# Private_CPU_Power.net
KiCad netlist of a schematic drawn in Altium Designer
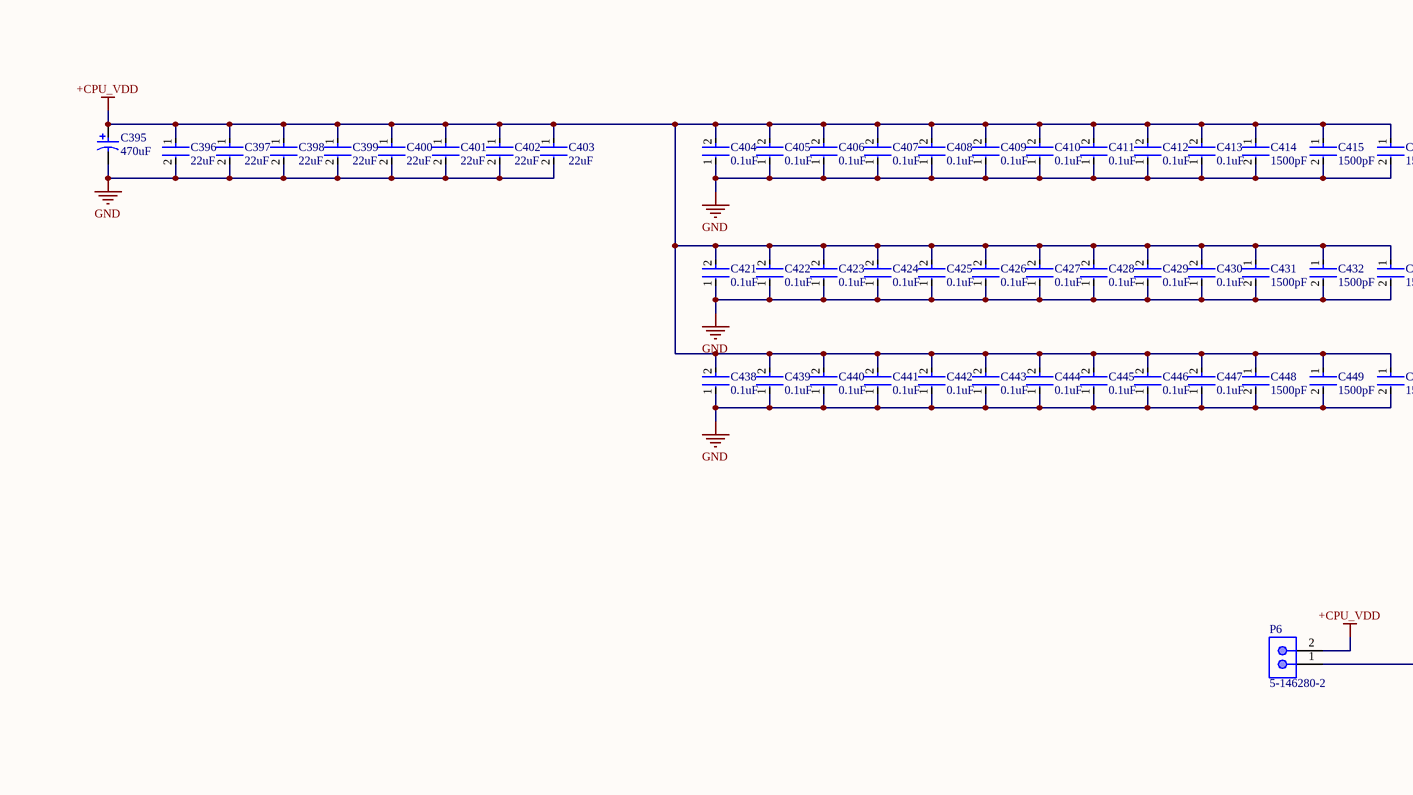
[diagram p0: Private_CPU_Power.SchDoc, top left]
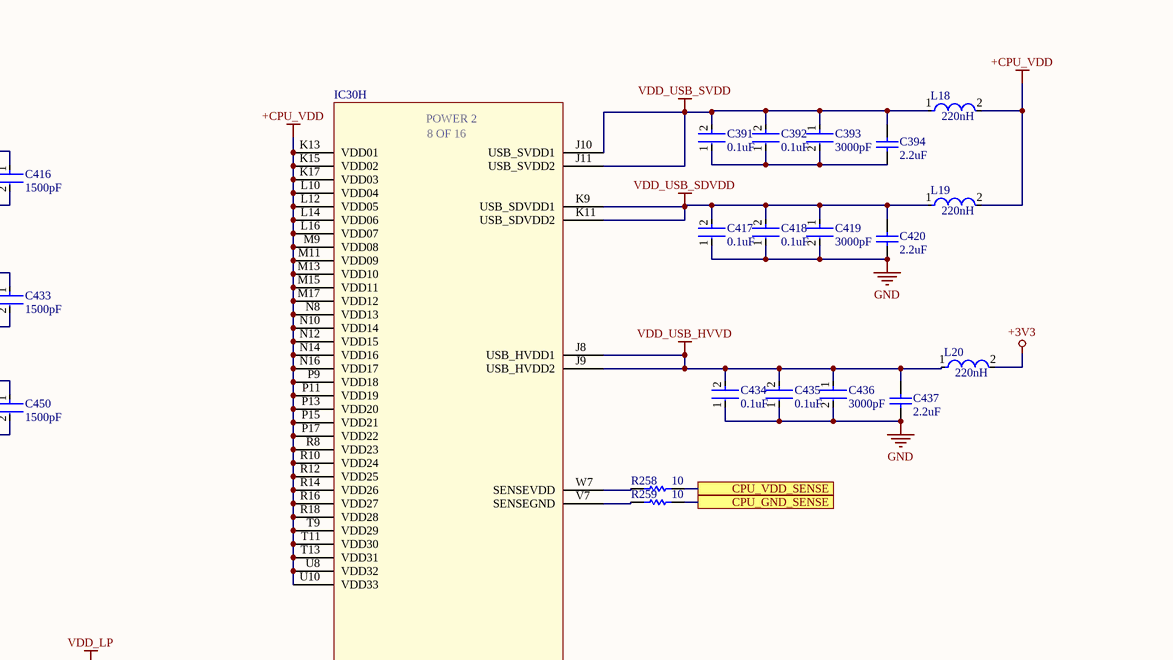
[diagram p1: Private_CPU_Power.SchDoc, top right]
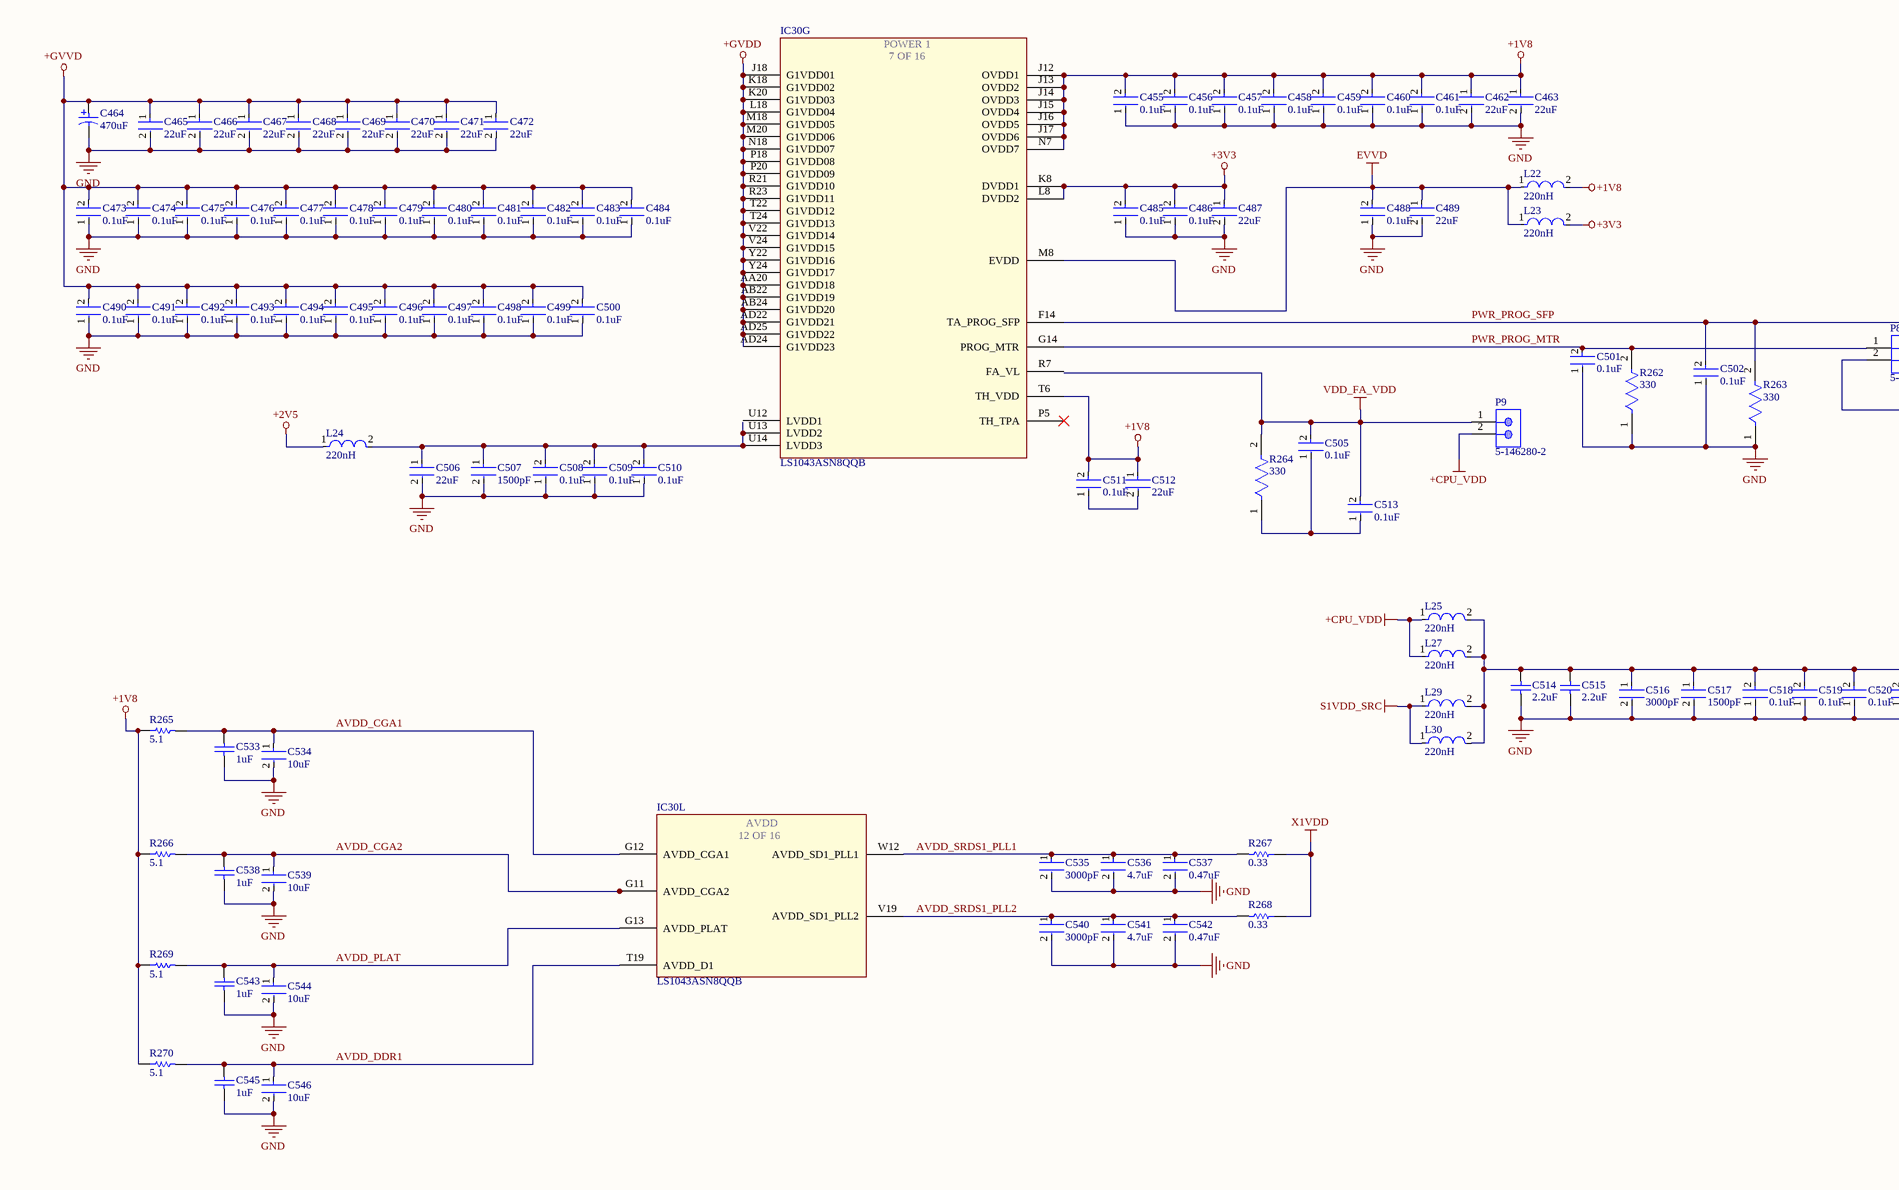
[diagram p2: Private_CPU_Power.SchDoc, bottom left]
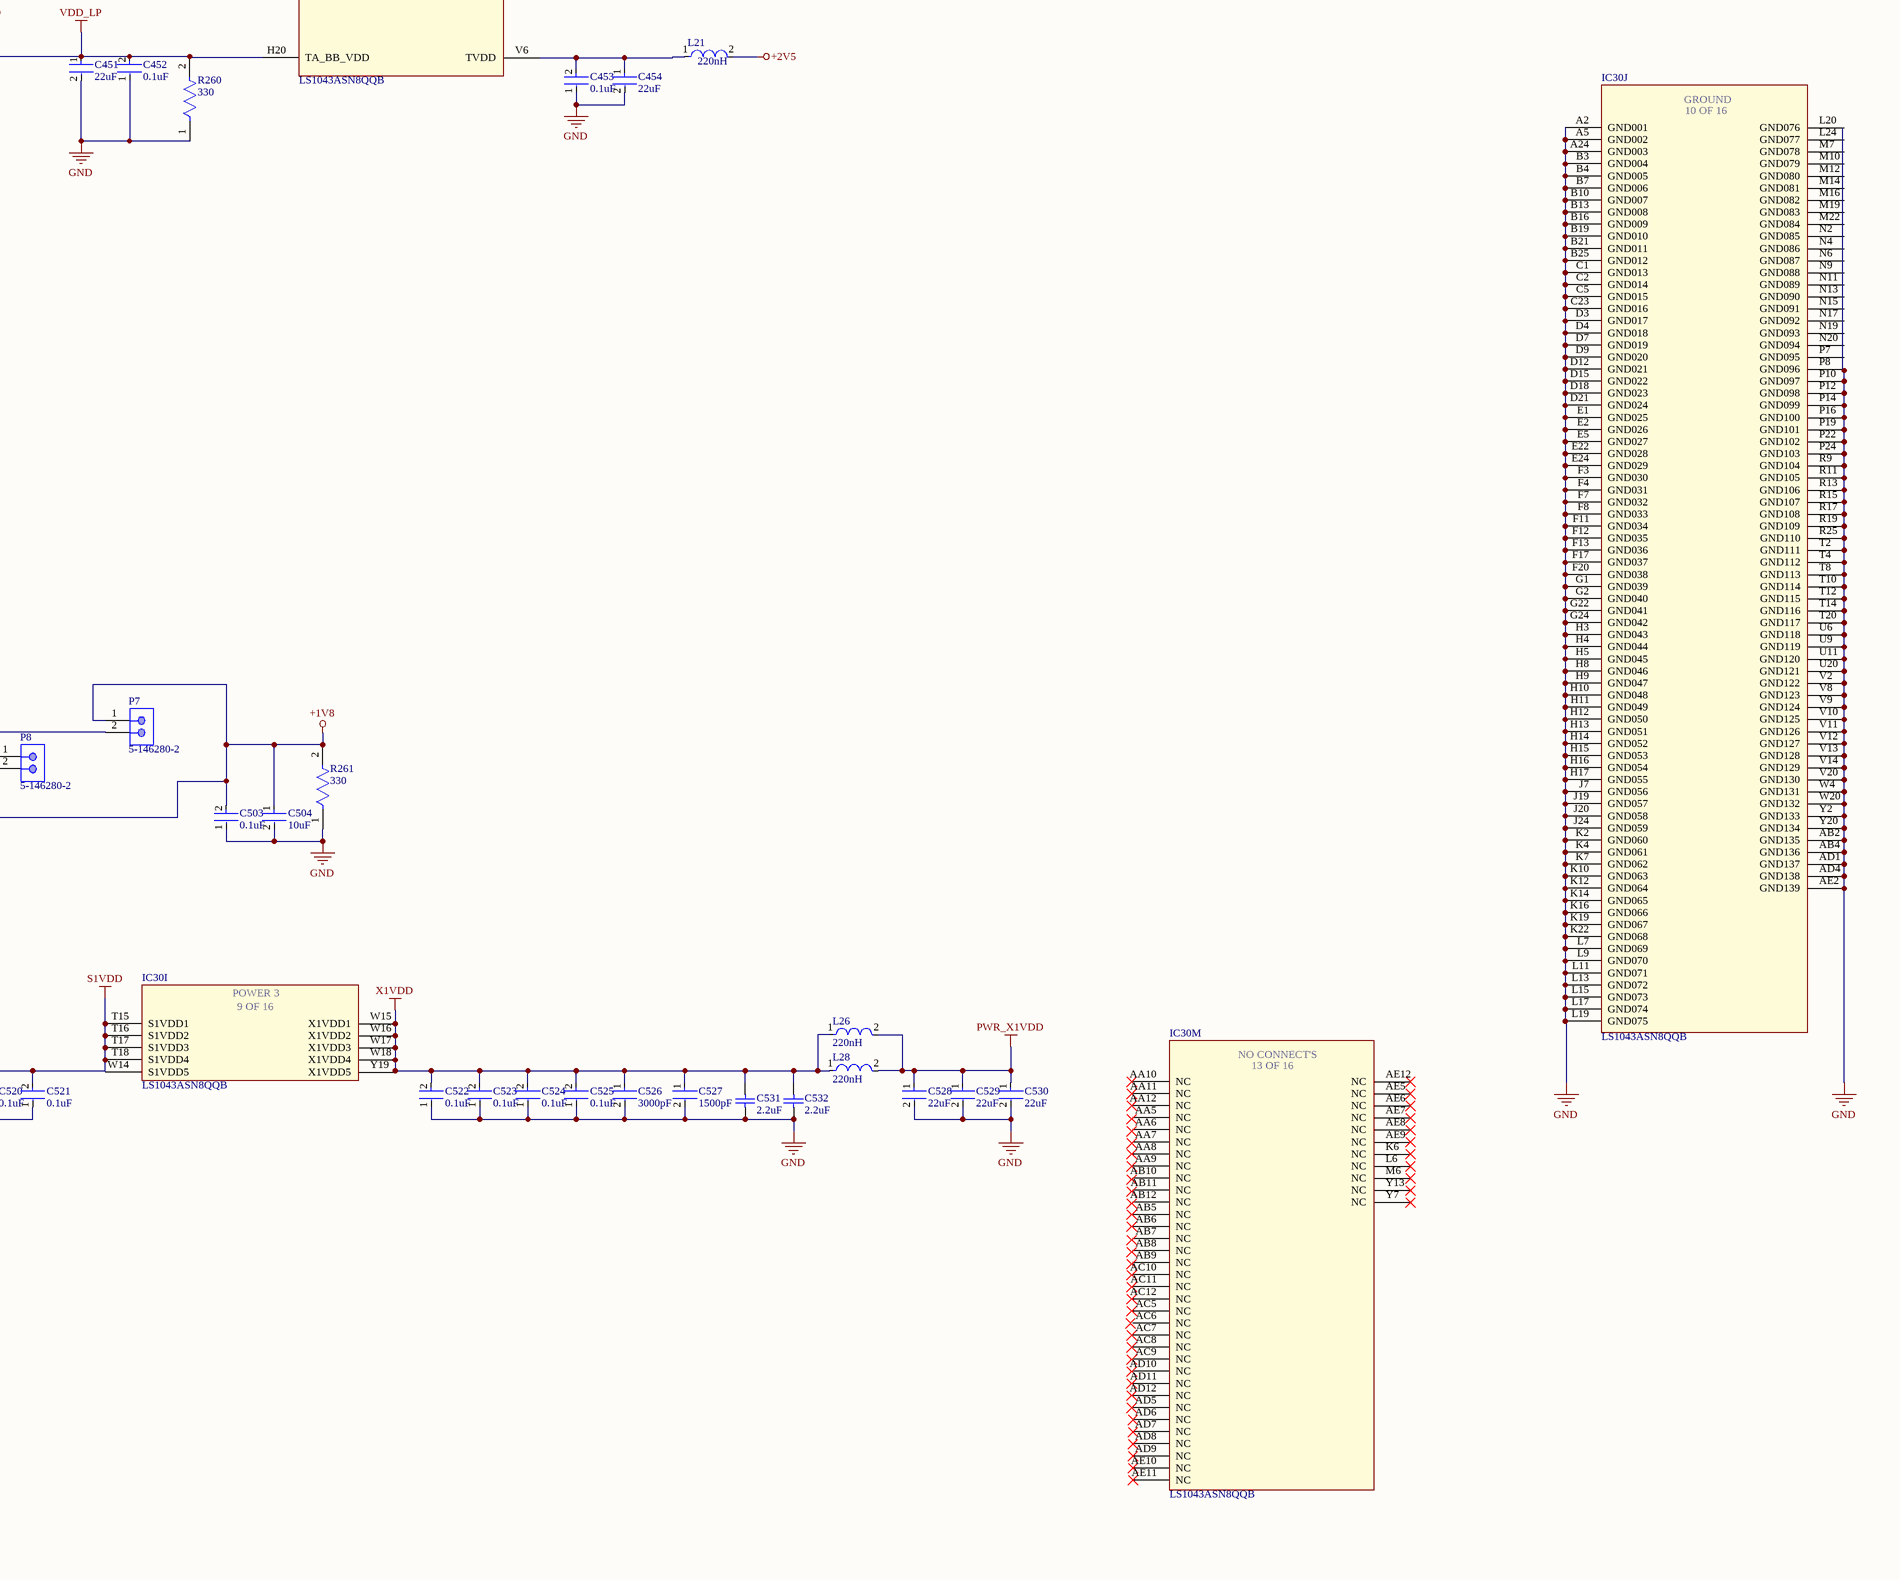
[diagram p3: Private_CPU_Power.SchDoc, bottom right]

(export (version "E")
  (design (tool "Eeschema 10.0.6"))
  (components
    (comp (ref "C391")
      (value "0.1uF")
      (footprint "FP-GRM15-MFG")
      (description "CAP CER 0.1UF 16V X7R 0402")
      (fields (field (name "MANUFACTURER PART NUMBER") "GRM155R71C104KA88D") (field (name "TOLERANCE") "10%"))
      (libsource (lib "Altium Content Vault") (part "236180d848d6139a670b325ea6854c9"))
    )
    (comp (ref "C392")
      (value "0.1uF")
      (footprint "FP-GRM15-MFG")
      (description "CAP CER 0.1UF 16V X7R 0402")
      (fields (field (name "MANUFACTURER PART NUMBER") "GRM155R71C104KA88D") (field (name "TOLERANCE") "10%"))
      (libsource (lib "Altium Content Vault") (part "236180d848d6139a670b325ea6854c9"))
    )
    (comp (ref "C393")
      (value "3000pF")
      (footprint "FP-GRM155-0_05-IPC_B")
      (description "Chip Multilayer Ceramic Capacitors for General Purpose, 0402, 3000pF, U2J, -750ppm/°C, 5%, 10V")
      (fields (field (name "TOLERANCE") "5%"))
      (libsource (lib "Altium Content Vault") (part "02cd4be3c70576c341d710602a673aa"))
    )
    (comp (ref "C394")
      (value "2.2uF")
      (footprint "CAPC1005X55X30NL05T10")
      (fields (field (name "MANUFACTURER") "Kemet") (field (name "PART NUMBER") "C0402C225M9PACTU"))
      (libsource (lib "Altium Content Vault") (part "CAP"))
    )
    (comp (ref "C395")
      (value "470uF")
      (footprint "PNSC-FK-V-F_V")
      (fields (field (name "MANUFACTURER") "Panasonic"))
      (libsource (lib "Altium Content Vault") (part "CAP-P-2"))
    )
    (comp (ref "C396")
      (value "22uF")
      (footprint "FP-GRM21B-0_15-MFG")
      (description "Chip Multilayer Ceramic Capacitors for General Purpose, 0805, 22uF, X5R, 15%, 20%, 6.3V")
      (fields (field (name "VOLTAGE") "6.3V") (field (name "TOLERANCE") "20%"))
      (libsource (lib "Altium Content Vault") (part "b4654b650e69147ec39a6b967a45e02"))
    )
    (comp (ref "C397")
      (value "22uF")
      (footprint "FP-GRM21B-0_15-MFG")
      (description "Chip Multilayer Ceramic Capacitors for General Purpose, 0805, 22uF, X5R, 15%, 20%, 6.3V")
      (fields (field (name "VOLTAGE") "6.3V") (field (name "TOLERANCE") "20%"))
      (libsource (lib "Altium Content Vault") (part "b4654b650e69147ec39a6b967a45e02"))
    )
    (comp (ref "C398")
      (value "22uF")
      (footprint "FP-GRM21B-0_15-MFG")
      (description "Chip Multilayer Ceramic Capacitors for General Purpose, 0805, 22uF, X5R, 15%, 20%, 6.3V")
      (fields (field (name "VOLTAGE") "6.3V") (field (name "TOLERANCE") "20%"))
      (libsource (lib "Altium Content Vault") (part "b4654b650e69147ec39a6b967a45e02"))
    )
    (comp (ref "C399")
      (value "22uF")
      (footprint "FP-GRM21B-0_15-MFG")
      (description "Chip Multilayer Ceramic Capacitors for General Purpose, 0805, 22uF, X5R, 15%, 20%, 6.3V")
      (fields (field (name "VOLTAGE") "6.3V") (field (name "TOLERANCE") "20%"))
      (libsource (lib "Altium Content Vault") (part "b4654b650e69147ec39a6b967a45e02"))
    )
    (comp (ref "C400")
      (value "22uF")
      (footprint "FP-GRM21B-0_15-MFG")
      (description "Chip Multilayer Ceramic Capacitors for General Purpose, 0805, 22uF, X5R, 15%, 20%, 6.3V")
      (fields (field (name "VOLTAGE") "6.3V") (field (name "TOLERANCE") "20%"))
      (libsource (lib "Altium Content Vault") (part "b4654b650e69147ec39a6b967a45e02"))
    )
    (comp (ref "C401")
      (value "22uF")
      (footprint "FP-GRM21B-0_15-MFG")
      (description "Chip Multilayer Ceramic Capacitors for General Purpose, 0805, 22uF, X5R, 15%, 20%, 6.3V")
      (fields (field (name "VOLTAGE") "6.3V") (field (name "TOLERANCE") "20%"))
      (libsource (lib "Altium Content Vault") (part "b4654b650e69147ec39a6b967a45e02"))
    )
    (comp (ref "C402")
      (value "22uF")
      (footprint "FP-GRM21B-0_15-MFG")
      (description "Chip Multilayer Ceramic Capacitors for General Purpose, 0805, 22uF, X5R, 15%, 20%, 6.3V")
      (fields (field (name "VOLTAGE") "6.3V") (field (name "TOLERANCE") "20%"))
      (libsource (lib "Altium Content Vault") (part "b4654b650e69147ec39a6b967a45e02"))
    )
    (comp (ref "C403")
      (value "22uF")
      (footprint "FP-GRM21B-0_15-MFG")
      (description "Chip Multilayer Ceramic Capacitors for General Purpose, 0805, 22uF, X5R, 15%, 20%, 6.3V")
      (fields (field (name "VOLTAGE") "6.3V") (field (name "TOLERANCE") "20%"))
      (libsource (lib "Altium Content Vault") (part "b4654b650e69147ec39a6b967a45e02"))
    )
    (comp (ref "C404")
      (value "0.1uF")
      (footprint "FP-GRM15-MFG")
      (description "CAP CER 0.1UF 16V X7R 0402")
      (fields (field (name "MANUFACTURER PART NUMBER") "GRM155R71C104KA88D") (field (name "TOLERANCE") "10%"))
      (libsource (lib "Altium Content Vault") (part "236180d848d6139a670b325ea6854c9"))
    )
    (comp (ref "C405")
      (value "0.1uF")
      (footprint "FP-GRM15-MFG")
      (description "CAP CER 0.1UF 16V X7R 0402")
      (fields (field (name "MANUFACTURER PART NUMBER") "GRM155R71C104KA88D") (field (name "TOLERANCE") "10%"))
      (libsource (lib "Altium Content Vault") (part "236180d848d6139a670b325ea6854c9"))
    )
    (comp (ref "C406")
      (value "0.1uF")
      (footprint "FP-GRM15-MFG")
      (description "CAP CER 0.1UF 16V X7R 0402")
      (fields (field (name "MANUFACTURER PART NUMBER") "GRM155R71C104KA88D") (field (name "TOLERANCE") "10%"))
      (libsource (lib "Altium Content Vault") (part "236180d848d6139a670b325ea6854c9"))
    )
    (comp (ref "C407")
      (value "0.1uF")
      (footprint "FP-GRM15-MFG")
      (description "CAP CER 0.1UF 16V X7R 0402")
      (fields (field (name "MANUFACTURER PART NUMBER") "GRM155R71C104KA88D") (field (name "TOLERANCE") "10%"))
      (libsource (lib "Altium Content Vault") (part "236180d848d6139a670b325ea6854c9"))
    )
    (comp (ref "C408")
      (value "0.1uF")
      (footprint "FP-GRM15-MFG")
      (description "CAP CER 0.1UF 16V X7R 0402")
      (fields (field (name "MANUFACTURER PART NUMBER") "GRM155R71C104KA88D") (field (name "TOLERANCE") "10%"))
      (libsource (lib "Altium Content Vault") (part "236180d848d6139a670b325ea6854c9"))
    )
    (comp (ref "C409")
      (value "0.1uF")
      (footprint "FP-GRM15-MFG")
      (description "CAP CER 0.1UF 16V X7R 0402")
      (fields (field (name "MANUFACTURER PART NUMBER") "GRM155R71C104KA88D") (field (name "TOLERANCE") "10%"))
      (libsource (lib "Altium Content Vault") (part "236180d848d6139a670b325ea6854c9"))
    )
    (comp (ref "C410")
      (value "0.1uF")
      (footprint "FP-GRM15-MFG")
      (description "CAP CER 0.1UF 16V X7R 0402")
      (fields (field (name "MANUFACTURER PART NUMBER") "GRM155R71C104KA88D") (field (name "TOLERANCE") "10%"))
      (libsource (lib "Altium Content Vault") (part "236180d848d6139a670b325ea6854c9"))
    )
    (comp (ref "C411")
      (value "0.1uF")
      (footprint "FP-GRM15-MFG")
      (description "CAP CER 0.1UF 16V X7R 0402")
      (fields (field (name "MANUFACTURER PART NUMBER") "GRM155R71C104KA88D") (field (name "TOLERANCE") "10%"))
      (libsource (lib "Altium Content Vault") (part "236180d848d6139a670b325ea6854c9"))
    )
    (comp (ref "C412")
      (value "0.1uF")
      (footprint "FP-GRM15-MFG")
      (description "CAP CER 0.1UF 16V X7R 0402")
      (fields (field (name "MANUFACTURER PART NUMBER") "GRM155R71C104KA88D") (field (name "TOLERANCE") "10%"))
      (libsource (lib "Altium Content Vault") (part "236180d848d6139a670b325ea6854c9"))
    )
    (comp (ref "C413")
      (value "0.1uF")
      (footprint "FP-GRM15-MFG")
      (description "CAP CER 0.1UF 16V X7R 0402")
      (fields (field (name "MANUFACTURER PART NUMBER") "GRM155R71C104KA88D") (field (name "TOLERANCE") "10%"))
      (libsource (lib "Altium Content Vault") (part "236180d848d6139a670b325ea6854c9"))
    )
    (comp (ref "C414")
      (value "1500pF")
      (footprint "FP-C0402-BB-MFG")
      (description "CAP CER 1500PF 50V X7R 0402")
      (fields
        (field (name "OCTOPART") "https://octopart.com/c0402c152k5ractu-kemet-125298")
        (field (name "TOLERANCE") "0.1")
      )
      (libsource (lib "Altium Content Vault") (part "b4654b650e69147ec39a6b967a45e02"))
    )
    (comp (ref "C415")
      (value "1500pF")
      (footprint "FP-C0402-BB-MFG")
      (description "CAP CER 1500PF 50V X7R 0402")
      (fields
        (field (name "OCTOPART") "https://octopart.com/c0402c152k5ractu-kemet-125298")
        (field (name "TOLERANCE") "0.1")
      )
      (libsource (lib "Altium Content Vault") (part "b4654b650e69147ec39a6b967a45e02"))
    )
    (comp (ref "C416")
      (value "1500pF")
      (footprint "FP-C0402-BB-MFG")
      (description "CAP CER 1500PF 50V X7R 0402")
      (fields
        (field (name "OCTOPART") "https://octopart.com/c0402c152k5ractu-kemet-125298")
        (field (name "TOLERANCE") "0.1")
      )
      (libsource (lib "Altium Content Vault") (part "b4654b650e69147ec39a6b967a45e02"))
    )
    (comp (ref "C417")
      (value "0.1uF")
      (footprint "FP-GRM15-MFG")
      (description "CAP CER 0.1UF 16V X7R 0402")
      (fields (field (name "MANUFACTURER PART NUMBER") "GRM155R71C104KA88D") (field (name "TOLERANCE") "10%"))
      (libsource (lib "Altium Content Vault") (part "236180d848d6139a670b325ea6854c9"))
    )
    (comp (ref "C418")
      (value "0.1uF")
      (footprint "FP-GRM15-MFG")
      (description "CAP CER 0.1UF 16V X7R 0402")
      (fields (field (name "MANUFACTURER PART NUMBER") "GRM155R71C104KA88D") (field (name "TOLERANCE") "10%"))
      (libsource (lib "Altium Content Vault") (part "236180d848d6139a670b325ea6854c9"))
    )
    (comp (ref "C419")
      (value "3000pF")
      (footprint "FP-GRM155-0_05-IPC_B")
      (description "Chip Multilayer Ceramic Capacitors for General Purpose, 0402, 3000pF, U2J, -750ppm/°C, 5%, 10V")
      (fields (field (name "TOLERANCE") "5%"))
      (libsource (lib "Altium Content Vault") (part "02cd4be3c70576c341d710602a673aa"))
    )
    (comp (ref "C420")
      (value "2.2uF")
      (footprint "CAPC1005X55X30NL05T10")
      (fields (field (name "MANUFACTURER") "Kemet") (field (name "PART NUMBER") "C0402C225M9PACTU"))
      (libsource (lib "Altium Content Vault") (part "CAP"))
    )
    (comp (ref "C421")
      (value "0.1uF")
      (footprint "FP-GRM15-MFG")
      (description "CAP CER 0.1UF 16V X7R 0402")
      (fields (field (name "MANUFACTURER PART NUMBER") "GRM155R71C104KA88D") (field (name "TOLERANCE") "10%"))
      (libsource (lib "Altium Content Vault") (part "236180d848d6139a670b325ea6854c9"))
    )
    (comp (ref "C422")
      (value "0.1uF")
      (footprint "FP-GRM15-MFG")
      (description "CAP CER 0.1UF 16V X7R 0402")
      (fields (field (name "MANUFACTURER PART NUMBER") "GRM155R71C104KA88D") (field (name "TOLERANCE") "10%"))
      (libsource (lib "Altium Content Vault") (part "236180d848d6139a670b325ea6854c9"))
    )
    (comp (ref "C423")
      (value "0.1uF")
      (footprint "FP-GRM15-MFG")
      (description "CAP CER 0.1UF 16V X7R 0402")
      (fields (field (name "MANUFACTURER PART NUMBER") "GRM155R71C104KA88D") (field (name "TOLERANCE") "10%"))
      (libsource (lib "Altium Content Vault") (part "236180d848d6139a670b325ea6854c9"))
    )
    (comp (ref "C424")
      (value "0.1uF")
      (footprint "FP-GRM15-MFG")
      (description "CAP CER 0.1UF 16V X7R 0402")
      (fields (field (name "MANUFACTURER PART NUMBER") "GRM155R71C104KA88D") (field (name "TOLERANCE") "10%"))
      (libsource (lib "Altium Content Vault") (part "236180d848d6139a670b325ea6854c9"))
    )
    (comp (ref "C425")
      (value "0.1uF")
      (footprint "FP-GRM15-MFG")
      (description "CAP CER 0.1UF 16V X7R 0402")
      (fields (field (name "MANUFACTURER PART NUMBER") "GRM155R71C104KA88D") (field (name "TOLERANCE") "10%"))
      (libsource (lib "Altium Content Vault") (part "236180d848d6139a670b325ea6854c9"))
    )
    (comp (ref "C426")
      (value "0.1uF")
      (footprint "FP-GRM15-MFG")
      (description "CAP CER 0.1UF 16V X7R 0402")
      (fields (field (name "MANUFACTURER PART NUMBER") "GRM155R71C104KA88D") (field (name "TOLERANCE") "10%"))
      (libsource (lib "Altium Content Vault") (part "236180d848d6139a670b325ea6854c9"))
    )
    (comp (ref "C427")
      (value "0.1uF")
      (footprint "FP-GRM15-MFG")
      (description "CAP CER 0.1UF 16V X7R 0402")
      (fields (field (name "MANUFACTURER PART NUMBER") "GRM155R71C104KA88D") (field (name "TOLERANCE") "10%"))
      (libsource (lib "Altium Content Vault") (part "236180d848d6139a670b325ea6854c9"))
    )
    (comp (ref "C428")
      (value "0.1uF")
      (footprint "FP-GRM15-MFG")
      (description "CAP CER 0.1UF 16V X7R 0402")
      (fields (field (name "MANUFACTURER PART NUMBER") "GRM155R71C104KA88D") (field (name "TOLERANCE") "10%"))
      (libsource (lib "Altium Content Vault") (part "236180d848d6139a670b325ea6854c9"))
    )
    (comp (ref "C429")
      (value "0.1uF")
      (footprint "FP-GRM15-MFG")
      (description "CAP CER 0.1UF 16V X7R 0402")
      (fields (field (name "MANUFACTURER PART NUMBER") "GRM155R71C104KA88D") (field (name "TOLERANCE") "10%"))
      (libsource (lib "Altium Content Vault") (part "236180d848d6139a670b325ea6854c9"))
    )
    (comp (ref "C430")
      (value "0.1uF")
      (footprint "FP-GRM15-MFG")
      (description "CAP CER 0.1UF 16V X7R 0402")
      (fields (field (name "MANUFACTURER PART NUMBER") "GRM155R71C104KA88D") (field (name "TOLERANCE") "10%"))
      (libsource (lib "Altium Content Vault") (part "236180d848d6139a670b325ea6854c9"))
    )
    (comp (ref "C431")
      (value "1500pF")
      (footprint "FP-C0402-BB-MFG")
      (description "CAP CER 1500PF 50V X7R 0402")
      (fields
        (field (name "OCTOPART") "https://octopart.com/c0402c152k5ractu-kemet-125298")
        (field (name "TOLERANCE") "0.1")
      )
      (libsource (lib "Altium Content Vault") (part "b4654b650e69147ec39a6b967a45e02"))
    )
    (comp (ref "C432")
      (value "1500pF")
      (footprint "FP-C0402-BB-MFG")
      (description "CAP CER 1500PF 50V X7R 0402")
      (fields
        (field (name "OCTOPART") "https://octopart.com/c0402c152k5ractu-kemet-125298")
        (field (name "TOLERANCE") "0.1")
      )
      (libsource (lib "Altium Content Vault") (part "b4654b650e69147ec39a6b967a45e02"))
    )
    (comp (ref "C433")
      (value "1500pF")
      (footprint "FP-C0402-BB-MFG")
      (description "CAP CER 1500PF 50V X7R 0402")
      (fields
        (field (name "OCTOPART") "https://octopart.com/c0402c152k5ractu-kemet-125298")
        (field (name "TOLERANCE") "0.1")
      )
      (libsource (lib "Altium Content Vault") (part "b4654b650e69147ec39a6b967a45e02"))
    )
    (comp (ref "C434")
      (value "0.1uF")
      (footprint "FP-GRM15-MFG")
      (description "CAP CER 0.1UF 16V X7R 0402")
      (fields (field (name "MANUFACTURER PART NUMBER") "GRM155R71C104KA88D") (field (name "TOLERANCE") "10%"))
      (libsource (lib "Altium Content Vault") (part "236180d848d6139a670b325ea6854c9"))
    )
    (comp (ref "C435")
      (value "0.1uF")
      (footprint "FP-GRM15-MFG")
      (description "CAP CER 0.1UF 16V X7R 0402")
      (fields (field (name "MANUFACTURER PART NUMBER") "GRM155R71C104KA88D") (field (name "TOLERANCE") "10%"))
      (libsource (lib "Altium Content Vault") (part "236180d848d6139a670b325ea6854c9"))
    )
    (comp (ref "C436")
      (value "3000pF")
      (footprint "FP-GRM155-0_05-IPC_B")
      (description "Chip Multilayer Ceramic Capacitors for General Purpose, 0402, 3000pF, U2J, -750ppm/°C, 5%, 10V")
      (fields (field (name "TOLERANCE") "5%"))
      (libsource (lib "Altium Content Vault") (part "02cd4be3c70576c341d710602a673aa"))
    )
    (comp (ref "C437")
      (value "2.2uF")
      (footprint "CAPC1005X55X30NL05T10")
      (fields (field (name "MANUFACTURER") "Kemet") (field (name "PART NUMBER") "C0402C225M9PACTU"))
      (libsource (lib "Altium Content Vault") (part "CAP"))
    )
    (comp (ref "C438")
      (value "0.1uF")
      (footprint "FP-GRM15-MFG")
      (description "CAP CER 0.1UF 16V X7R 0402")
      (fields (field (name "MANUFACTURER PART NUMBER") "GRM155R71C104KA88D") (field (name "TOLERANCE") "10%"))
      (libsource (lib "Altium Content Vault") (part "236180d848d6139a670b325ea6854c9"))
    )
    (comp (ref "C439")
      (value "0.1uF")
      (footprint "FP-GRM15-MFG")
      (description "CAP CER 0.1UF 16V X7R 0402")
      (fields (field (name "MANUFACTURER PART NUMBER") "GRM155R71C104KA88D") (field (name "TOLERANCE") "10%"))
      (libsource (lib "Altium Content Vault") (part "236180d848d6139a670b325ea6854c9"))
    )
    (comp (ref "C440")
      (value "0.1uF")
      (footprint "FP-GRM15-MFG")
      (description "CAP CER 0.1UF 16V X7R 0402")
      (fields (field (name "MANUFACTURER PART NUMBER") "GRM155R71C104KA88D") (field (name "TOLERANCE") "10%"))
      (libsource (lib "Altium Content Vault") (part "236180d848d6139a670b325ea6854c9"))
    )
    (comp (ref "C441")
      (value "0.1uF")
      (footprint "FP-GRM15-MFG")
      (description "CAP CER 0.1UF 16V X7R 0402")
      (fields (field (name "MANUFACTURER PART NUMBER") "GRM155R71C104KA88D") (field (name "TOLERANCE") "10%"))
      (libsource (lib "Altium Content Vault") (part "236180d848d6139a670b325ea6854c9"))
    )
    (comp (ref "C442")
      (value "0.1uF")
      (footprint "FP-GRM15-MFG")
      (description "CAP CER 0.1UF 16V X7R 0402")
      (fields (field (name "MANUFACTURER PART NUMBER") "GRM155R71C104KA88D") (field (name "TOLERANCE") "10%"))
      (libsource (lib "Altium Content Vault") (part "236180d848d6139a670b325ea6854c9"))
    )
    (comp (ref "C443")
      (value "0.1uF")
      (footprint "FP-GRM15-MFG")
      (description "CAP CER 0.1UF 16V X7R 0402")
      (fields (field (name "MANUFACTURER PART NUMBER") "GRM155R71C104KA88D") (field (name "TOLERANCE") "10%"))
      (libsource (lib "Altium Content Vault") (part "236180d848d6139a670b325ea6854c9"))
    )
    (comp (ref "C444")
      (value "0.1uF")
      (footprint "FP-GRM15-MFG")
      (description "CAP CER 0.1UF 16V X7R 0402")
      (fields (field (name "MANUFACTURER PART NUMBER") "GRM155R71C104KA88D") (field (name "TOLERANCE") "10%"))
      (libsource (lib "Altium Content Vault") (part "236180d848d6139a670b325ea6854c9"))
    )
    (comp (ref "C445")
      (value "0.1uF")
      (footprint "FP-GRM15-MFG")
      (description "CAP CER 0.1UF 16V X7R 0402")
      (fields (field (name "MANUFACTURER PART NUMBER") "GRM155R71C104KA88D") (field (name "TOLERANCE") "10%"))
      (libsource (lib "Altium Content Vault") (part "236180d848d6139a670b325ea6854c9"))
    )
    (comp (ref "C446")
      (value "0.1uF")
      (footprint "FP-GRM15-MFG")
      (description "CAP CER 0.1UF 16V X7R 0402")
      (fields (field (name "MANUFACTURER PART NUMBER") "GRM155R71C104KA88D") (field (name "TOLERANCE") "10%"))
      (libsource (lib "Altium Content Vault") (part "236180d848d6139a670b325ea6854c9"))
    )
    (comp (ref "C447")
      (value "0.1uF")
      (footprint "FP-GRM15-MFG")
      (description "CAP CER 0.1UF 16V X7R 0402")
      (fields (field (name "MANUFACTURER PART NUMBER") "GRM155R71C104KA88D") (field (name "TOLERANCE") "10%"))
      (libsource (lib "Altium Content Vault") (part "236180d848d6139a670b325ea6854c9"))
    )
    (comp (ref "C448")
      (value "1500pF")
      (footprint "FP-C0402-BB-MFG")
      (description "CAP CER 1500PF 50V X7R 0402")
      (fields
        (field (name "OCTOPART") "https://octopart.com/c0402c152k5ractu-kemet-125298")
        (field (name "TOLERANCE") "0.1")
      )
      (libsource (lib "Altium Content Vault") (part "b4654b650e69147ec39a6b967a45e02"))
    )
    (comp (ref "C449")
      (value "1500pF")
      (footprint "FP-C0402-BB-MFG")
      (description "CAP CER 1500PF 50V X7R 0402")
      (fields
        (field (name "OCTOPART") "https://octopart.com/c0402c152k5ractu-kemet-125298")
        (field (name "TOLERANCE") "0.1")
      )
      (libsource (lib "Altium Content Vault") (part "b4654b650e69147ec39a6b967a45e02"))
    )
    (comp (ref "C450")
      (value "1500pF")
      (footprint "FP-C0402-BB-MFG")
      (description "CAP CER 1500PF 50V X7R 0402")
      (fields
        (field (name "OCTOPART") "https://octopart.com/c0402c152k5ractu-kemet-125298")
        (field (name "TOLERANCE") "0.1")
      )
      (libsource (lib "Altium Content Vault") (part "b4654b650e69147ec39a6b967a45e02"))
    )
    (comp (ref "C451")
      (value "22uF")
      (footprint "FP-GRM21B-0_15-MFG")
      (description "Chip Multilayer Ceramic Capacitors for General Purpose, 0805, 22uF, X5R, 15%, 20%, 6.3V")
      (fields (field (name "VOLTAGE") "6.3V") (field (name "TOLERANCE") "20%"))
      (libsource (lib "Altium Content Vault") (part "b4654b650e69147ec39a6b967a45e02"))
    )
    (comp (ref "C452")
      (value "0.1uF")
      (footprint "FP-GRM15-MFG")
      (description "CAP CER 0.1UF 16V X7R 0402")
      (fields (field (name "MANUFACTURER PART NUMBER") "GRM155R71C104KA88D") (field (name "TOLERANCE") "10%"))
      (libsource (lib "Altium Content Vault") (part "236180d848d6139a670b325ea6854c9"))
    )
    (comp (ref "C453")
      (value "0.1uF")
      (footprint "FP-GRM15-MFG")
      (description "CAP CER 0.1UF 16V X7R 0402")
      (fields (field (name "MANUFACTURER PART NUMBER") "GRM155R71C104KA88D") (field (name "TOLERANCE") "10%"))
      (libsource (lib "Altium Content Vault") (part "236180d848d6139a670b325ea6854c9"))
    )
    (comp (ref "C454")
      (value "22uF")
      (footprint "FP-GRM21B-0_15-MFG")
      (description "Chip Multilayer Ceramic Capacitors for General Purpose, 0805, 22uF, X5R, 15%, 20%, 6.3V")
      (fields (field (name "VOLTAGE") "6.3V") (field (name "TOLERANCE") "20%"))
      (libsource (lib "Altium Content Vault") (part "b4654b650e69147ec39a6b967a45e02"))
    )
    (comp (ref "C455")
      (value "0.1uF")
      (footprint "FP-GRM15-MFG")
      (description "CAP CER 0.1UF 16V X7R 0402")
      (fields (field (name "MANUFACTURER PART NUMBER") "GRM155R71C104KA88D") (field (name "TOLERANCE") "10%"))
      (libsource (lib "Altium Content Vault") (part "236180d848d6139a670b325ea6854c9"))
    )
    (comp (ref "C456")
      (value "0.1uF")
      (footprint "FP-GRM15-MFG")
      (description "CAP CER 0.1UF 16V X7R 0402")
      (fields (field (name "MANUFACTURER PART NUMBER") "GRM155R71C104KA88D") (field (name "TOLERANCE") "10%"))
      (libsource (lib "Altium Content Vault") (part "236180d848d6139a670b325ea6854c9"))
    )
    (comp (ref "C457")
      (value "0.1uF")
      (footprint "FP-GRM15-MFG")
      (description "CAP CER 0.1UF 16V X7R 0402")
      (fields (field (name "MANUFACTURER PART NUMBER") "GRM155R71C104KA88D") (field (name "TOLERANCE") "10%"))
      (libsource (lib "Altium Content Vault") (part "236180d848d6139a670b325ea6854c9"))
    )
    (comp (ref "C458")
      (value "0.1uF")
      (footprint "FP-GRM15-MFG")
      (description "CAP CER 0.1UF 16V X7R 0402")
      (fields (field (name "MANUFACTURER PART NUMBER") "GRM155R71C104KA88D") (field (name "TOLERANCE") "10%"))
      (libsource (lib "Altium Content Vault") (part "236180d848d6139a670b325ea6854c9"))
    )
    (comp (ref "C459")
      (value "0.1uF")
      (footprint "FP-GRM15-MFG")
      (description "CAP CER 0.1UF 16V X7R 0402")
      (fields (field (name "MANUFACTURER PART NUMBER") "GRM155R71C104KA88D") (field (name "TOLERANCE") "10%"))
      (libsource (lib "Altium Content Vault") (part "236180d848d6139a670b325ea6854c9"))
    )
    (comp (ref "C460")
      (value "0.1uF")
      (footprint "FP-GRM15-MFG")
      (description "CAP CER 0.1UF 16V X7R 0402")
      (fields (field (name "MANUFACTURER PART NUMBER") "GRM155R71C104KA88D") (field (name "TOLERANCE") "10%"))
      (libsource (lib "Altium Content Vault") (part "236180d848d6139a670b325ea6854c9"))
    )
    (comp (ref "C461")
      (value "0.1uF")
      (footprint "FP-GRM15-MFG")
      (description "CAP CER 0.1UF 16V X7R 0402")
      (fields (field (name "MANUFACTURER PART NUMBER") "GRM155R71C104KA88D") (field (name "TOLERANCE") "10%"))
      (libsource (lib "Altium Content Vault") (part "236180d848d6139a670b325ea6854c9"))
    )
    (comp (ref "C462")
      (value "22uF")
      (footprint "FP-GRM21B-0_15-MFG")
      (description "Chip Multilayer Ceramic Capacitors for General Purpose, 0805, 22uF, X5R, 15%, 20%, 6.3V")
      (fields (field (name "VOLTAGE") "6.3V") (field (name "TOLERANCE") "20%"))
      (libsource (lib "Altium Content Vault") (part "b4654b650e69147ec39a6b967a45e02"))
    )
    (comp (ref "C463")
      (value "22uF")
      (footprint "FP-GRM21B-0_15-MFG")
      (description "Chip Multilayer Ceramic Capacitors for General Purpose, 0805, 22uF, X5R, 15%, 20%, 6.3V")
      (fields (field (name "VOLTAGE") "6.3V") (field (name "TOLERANCE") "20%"))
      (libsource (lib "Altium Content Vault") (part "b4654b650e69147ec39a6b967a45e02"))
    )
    (comp (ref "C464")
      (value "470uF")
      (footprint "PNSC-FK-V-F_V")
      (fields (field (name "MANUFACTURER") "Panasonic"))
      (libsource (lib "Altium Content Vault") (part "CAP-P-2"))
    )
    (comp (ref "C465")
      (value "22uF")
      (footprint "FP-GRM21B-0_15-MFG")
      (description "Chip Multilayer Ceramic Capacitors for General Purpose, 0805, 22uF, X5R, 15%, 20%, 6.3V")
      (fields (field (name "VOLTAGE") "6.3V") (field (name "TOLERANCE") "20%"))
      (libsource (lib "Altium Content Vault") (part "b4654b650e69147ec39a6b967a45e02"))
    )
    (comp (ref "C466")
      (value "22uF")
      (footprint "FP-GRM21B-0_15-MFG")
      (description "Chip Multilayer Ceramic Capacitors for General Purpose, 0805, 22uF, X5R, 15%, 20%, 6.3V")
      (fields (field (name "VOLTAGE") "6.3V") (field (name "TOLERANCE") "20%"))
      (libsource (lib "Altium Content Vault") (part "b4654b650e69147ec39a6b967a45e02"))
    )
    (comp (ref "C467")
      (value "22uF")
      (footprint "FP-GRM21B-0_15-MFG")
      (description "Chip Multilayer Ceramic Capacitors for General Purpose, 0805, 22uF, X5R, 15%, 20%, 6.3V")
      (fields (field (name "VOLTAGE") "6.3V") (field (name "TOLERANCE") "20%"))
      (libsource (lib "Altium Content Vault") (part "b4654b650e69147ec39a6b967a45e02"))
    )
    (comp (ref "C468")
      (value "22uF")
      (footprint "FP-GRM21B-0_15-MFG")
      (description "Chip Multilayer Ceramic Capacitors for General Purpose, 0805, 22uF, X5R, 15%, 20%, 6.3V")
      (fields (field (name "VOLTAGE") "6.3V") (field (name "TOLERANCE") "20%"))
      (libsource (lib "Altium Content Vault") (part "b4654b650e69147ec39a6b967a45e02"))
    )
    (comp (ref "C469")
      (value "22uF")
      (footprint "FP-GRM21B-0_15-MFG")
      (description "Chip Multilayer Ceramic Capacitors for General Purpose, 0805, 22uF, X5R, 15%, 20%, 6.3V")
      (fields (field (name "VOLTAGE") "6.3V") (field (name "TOLERANCE") "20%"))
      (libsource (lib "Altium Content Vault") (part "b4654b650e69147ec39a6b967a45e02"))
    )
    (comp (ref "C470")
      (value "22uF")
      (footprint "FP-GRM21B-0_15-MFG")
      (description "Chip Multilayer Ceramic Capacitors for General Purpose, 0805, 22uF, X5R, 15%, 20%, 6.3V")
      (fields (field (name "VOLTAGE") "6.3V") (field (name "TOLERANCE") "20%"))
      (libsource (lib "Altium Content Vault") (part "b4654b650e69147ec39a6b967a45e02"))
    )
    (comp (ref "C471")
      (value "22uF")
      (footprint "FP-GRM21B-0_15-MFG")
      (description "Chip Multilayer Ceramic Capacitors for General Purpose, 0805, 22uF, X5R, 15%, 20%, 6.3V")
      (fields (field (name "VOLTAGE") "6.3V") (field (name "TOLERANCE") "20%"))
      (libsource (lib "Altium Content Vault") (part "b4654b650e69147ec39a6b967a45e02"))
    )
    (comp (ref "C472")
      (value "22uF")
      (footprint "FP-GRM21B-0_15-MFG")
      (description "Chip Multilayer Ceramic Capacitors for General Purpose, 0805, 22uF, X5R, 15%, 20%, 6.3V")
      (fields (field (name "VOLTAGE") "6.3V") (field (name "TOLERANCE") "20%"))
      (libsource (lib "Altium Content Vault") (part "b4654b650e69147ec39a6b967a45e02"))
    )
    (comp (ref "C473")
      (value "0.1uF")
      (footprint "FP-GRM15-MFG")
      (description "CAP CER 0.1UF 16V X7R 0402")
      (fields (field (name "MANUFACTURER PART NUMBER") "GRM155R71C104KA88D") (field (name "TOLERANCE") "10%"))
      (libsource (lib "Altium Content Vault") (part "236180d848d6139a670b325ea6854c9"))
    )
    (comp (ref "C474")
      (value "0.1uF")
      (footprint "FP-GRM15-MFG")
      (description "CAP CER 0.1UF 16V X7R 0402")
      (fields (field (name "MANUFACTURER PART NUMBER") "GRM155R71C104KA88D") (field (name "TOLERANCE") "10%"))
      (libsource (lib "Altium Content Vault") (part "236180d848d6139a670b325ea6854c9"))
    )
    (comp (ref "C475")
      (value "0.1uF")
      (footprint "FP-GRM15-MFG")
      (description "CAP CER 0.1UF 16V X7R 0402")
      (fields (field (name "MANUFACTURER PART NUMBER") "GRM155R71C104KA88D") (field (name "TOLERANCE") "10%"))
      (libsource (lib "Altium Content Vault") (part "236180d848d6139a670b325ea6854c9"))
    )
    (comp (ref "C476")
      (value "0.1uF")
      (footprint "FP-GRM15-MFG")
      (description "CAP CER 0.1UF 16V X7R 0402")
      (fields (field (name "MANUFACTURER PART NUMBER") "GRM155R71C104KA88D") (field (name "TOLERANCE") "10%"))
      (libsource (lib "Altium Content Vault") (part "236180d848d6139a670b325ea6854c9"))
    )
    (comp (ref "C477")
      (value "0.1uF")
      (footprint "FP-GRM15-MFG")
      (description "CAP CER 0.1UF 16V X7R 0402")
      (fields (field (name "MANUFACTURER PART NUMBER") "GRM155R71C104KA88D") (field (name "TOLERANCE") "10%"))
      (libsource (lib "Altium Content Vault") (part "236180d848d6139a670b325ea6854c9"))
    )
    (comp (ref "C478")
      (value "0.1uF")
      (footprint "FP-GRM15-MFG")
      (description "CAP CER 0.1UF 16V X7R 0402")
      (fields (field (name "MANUFACTURER PART NUMBER") "GRM155R71C104KA88D") (field (name "TOLERANCE") "10%"))
      (libsource (lib "Altium Content Vault") (part "236180d848d6139a670b325ea6854c9"))
    )
    (comp (ref "C479")
      (value "0.1uF")
      (footprint "FP-GRM15-MFG")
      (description "CAP CER 0.1UF 16V X7R 0402")
      (fields (field (name "MANUFACTURER PART NUMBER") "GRM155R71C104KA88D") (field (name "TOLERANCE") "10%"))
      (libsource (lib "Altium Content Vault") (part "236180d848d6139a670b325ea6854c9"))
    )
    (comp (ref "C480")
      (value "0.1uF")
      (footprint "FP-GRM15-MFG")
      (description "CAP CER 0.1UF 16V X7R 0402")
      (fields (field (name "MANUFACTURER PART NUMBER") "GRM155R71C104KA88D") (field (name "TOLERANCE") "10%"))
      (libsource (lib "Altium Content Vault") (part "236180d848d6139a670b325ea6854c9"))
    )
    (comp (ref "C481")
      (value "0.1uF")
      (footprint "FP-GRM15-MFG")
      (description "CAP CER 0.1UF 16V X7R 0402")
      (fields (field (name "MANUFACTURER PART NUMBER") "GRM155R71C104KA88D") (field (name "TOLERANCE") "10%"))
      (libsource (lib "Altium Content Vault") (part "236180d848d6139a670b325ea6854c9"))
    )
    (comp (ref "C482")
      (value "0.1uF")
      (footprint "FP-GRM15-MFG")
      (description "CAP CER 0.1UF 16V X7R 0402")
      (fields (field (name "MANUFACTURER PART NUMBER") "GRM155R71C104KA88D") (field (name "TOLERANCE") "10%"))
      (libsource (lib "Altium Content Vault") (part "236180d848d6139a670b325ea6854c9"))
    )
    (comp (ref "C483")
      (value "0.1uF")
      (footprint "FP-GRM15-MFG")
      (description "CAP CER 0.1UF 16V X7R 0402")
      (fields (field (name "MANUFACTURER PART NUMBER") "GRM155R71C104KA88D") (field (name "TOLERANCE") "10%"))
      (libsource (lib "Altium Content Vault") (part "236180d848d6139a670b325ea6854c9"))
    )
    (comp (ref "C484")
      (value "0.1uF")
      (footprint "FP-GRM15-MFG")
      (description "CAP CER 0.1UF 16V X7R 0402")
      (fields (field (name "MANUFACTURER PART NUMBER") "GRM155R71C104KA88D") (field (name "TOLERANCE") "10%"))
      (libsource (lib "Altium Content Vault") (part "236180d848d6139a670b325ea6854c9"))
    )
    (comp (ref "C485")
      (value "0.1uF")
      (footprint "FP-GRM15-MFG")
      (description "CAP CER 0.1UF 16V X7R 0402")
      (fields (field (name "MANUFACTURER PART NUMBER") "GRM155R71C104KA88D") (field (name "TOLERANCE") "10%"))
      (libsource (lib "Altium Content Vault") (part "236180d848d6139a670b325ea6854c9"))
    )
    (comp (ref "C486")
      (value "0.1uF")
      (footprint "FP-GRM15-MFG")
      (description "CAP CER 0.1UF 16V X7R 0402")
      (fields (field (name "MANUFACTURER PART NUMBER") "GRM155R71C104KA88D") (field (name "TOLERANCE") "10%"))
      (libsource (lib "Altium Content Vault") (part "236180d848d6139a670b325ea6854c9"))
    )
    (comp (ref "C487")
      (value "22uF")
      (footprint "FP-GRM21B-0_15-MFG")
      (description "Chip Multilayer Ceramic Capacitors for General Purpose, 0805, 22uF, X5R, 15%, 20%, 6.3V")
      (fields (field (name "VOLTAGE") "6.3V") (field (name "TOLERANCE") "20%"))
      (libsource (lib "Altium Content Vault") (part "b4654b650e69147ec39a6b967a45e02"))
    )
    (comp (ref "C488")
      (value "0.1uF")
      (footprint "FP-GRM15-MFG")
      (description "CAP CER 0.1UF 16V X7R 0402")
      (fields (field (name "MANUFACTURER PART NUMBER") "GRM155R71C104KA88D") (field (name "TOLERANCE") "10%"))
      (libsource (lib "Altium Content Vault") (part "236180d848d6139a670b325ea6854c9"))
    )
    (comp (ref "C489")
      (value "22uF")
      (footprint "FP-GRM21B-0_15-MFG")
      (description "Chip Multilayer Ceramic Capacitors for General Purpose, 0805, 22uF, X5R, 15%, 20%, 6.3V")
      (fields (field (name "VOLTAGE") "6.3V") (field (name "TOLERANCE") "20%"))
      (libsource (lib "Altium Content Vault") (part "b4654b650e69147ec39a6b967a45e02"))
    )
    (comp (ref "C490")
      (value "0.1uF")
      (footprint "FP-GRM15-MFG")
      (description "CAP CER 0.1UF 16V X7R 0402")
      (fields (field (name "MANUFACTURER PART NUMBER") "GRM155R71C104KA88D") (field (name "TOLERANCE") "10%"))
      (libsource (lib "Altium Content Vault") (part "236180d848d6139a670b325ea6854c9"))
    )
    (comp (ref "C491")
      (value "0.1uF")
      (footprint "FP-GRM15-MFG")
      (description "CAP CER 0.1UF 16V X7R 0402")
      (fields (field (name "MANUFACTURER PART NUMBER") "GRM155R71C104KA88D") (field (name "TOLERANCE") "10%"))
      (libsource (lib "Altium Content Vault") (part "236180d848d6139a670b325ea6854c9"))
    )
    (comp (ref "C492")
      (value "0.1uF")
      (footprint "FP-GRM15-MFG")
      (description "CAP CER 0.1UF 16V X7R 0402")
      (fields (field (name "MANUFACTURER PART NUMBER") "GRM155R71C104KA88D") (field (name "TOLERANCE") "10%"))
      (libsource (lib "Altium Content Vault") (part "236180d848d6139a670b325ea6854c9"))
    )
    (comp (ref "C493")
      (value "0.1uF")
      (footprint "FP-GRM15-MFG")
      (description "CAP CER 0.1UF 16V X7R 0402")
      (fields (field (name "MANUFACTURER PART NUMBER") "GRM155R71C104KA88D") (field (name "TOLERANCE") "10%"))
      (libsource (lib "Altium Content Vault") (part "236180d848d6139a670b325ea6854c9"))
    )
    (comp (ref "C494")
      (value "0.1uF")
      (footprint "FP-GRM15-MFG")
      (description "CAP CER 0.1UF 16V X7R 0402")
      (fields (field (name "MANUFACTURER PART NUMBER") "GRM155R71C104KA88D") (field (name "TOLERANCE") "10%"))
      (libsource (lib "Altium Content Vault") (part "236180d848d6139a670b325ea6854c9"))
    )
    (comp (ref "C495")
      (value "0.1uF")
      (footprint "FP-GRM15-MFG")
      (description "CAP CER 0.1UF 16V X7R 0402")
      (fields (field (name "MANUFACTURER PART NUMBER") "GRM155R71C104KA88D") (field (name "TOLERANCE") "10%"))
      (libsource (lib "Altium Content Vault") (part "236180d848d6139a670b325ea6854c9"))
    )
    (comp (ref "C496")
      (value "0.1uF")
      (footprint "FP-GRM15-MFG")
      (description "CAP CER 0.1UF 16V X7R 0402")
      (fields (field (name "MANUFACTURER PART NUMBER") "GRM155R71C104KA88D") (field (name "TOLERANCE") "10%"))
      (libsource (lib "Altium Content Vault") (part "236180d848d6139a670b325ea6854c9"))
    )
    (comp (ref "C497")
      (value "0.1uF")
      (footprint "FP-GRM15-MFG")
      (description "CAP CER 0.1UF 16V X7R 0402")
      (fields (field (name "MANUFACTURER PART NUMBER") "GRM155R71C104KA88D") (field (name "TOLERANCE") "10%"))
      (libsource (lib "Altium Content Vault") (part "236180d848d6139a670b325ea6854c9"))
    )
    (comp (ref "C498")
      (value "0.1uF")
      (footprint "FP-GRM15-MFG")
      (description "CAP CER 0.1UF 16V X7R 0402")
      (fields (field (name "MANUFACTURER PART NUMBER") "GRM155R71C104KA88D") (field (name "TOLERANCE") "10%"))
      (libsource (lib "Altium Content Vault") (part "236180d848d6139a670b325ea6854c9"))
    )
    (comp (ref "C499")
      (value "0.1uF")
      (footprint "FP-GRM15-MFG")
      (description "CAP CER 0.1UF 16V X7R 0402")
      (fields (field (name "MANUFACTURER PART NUMBER") "GRM155R71C104KA88D") (field (name "TOLERANCE") "10%"))
      (libsource (lib "Altium Content Vault") (part "236180d848d6139a670b325ea6854c9"))
    )
    (comp (ref "C500")
      (value "0.1uF")
      (footprint "FP-GRM15-MFG")
      (description "CAP CER 0.1UF 16V X7R 0402")
      (fields (field (name "MANUFACTURER PART NUMBER") "GRM155R71C104KA88D") (field (name "TOLERANCE") "10%"))
      (libsource (lib "Altium Content Vault") (part "236180d848d6139a670b325ea6854c9"))
    )
    (comp (ref "C501")
      (value "0.1uF")
      (footprint "FP-GRM15-MFG")
      (description "CAP CER 0.1UF 16V X7R 0402")
      (fields (field (name "MANUFACTURER PART NUMBER") "GRM155R71C104KA88D") (field (name "TOLERANCE") "10%"))
      (libsource (lib "Altium Content Vault") (part "236180d848d6139a670b325ea6854c9"))
    )
    (comp (ref "C502")
      (value "0.1uF")
      (footprint "FP-GRM15-MFG")
      (description "CAP CER 0.1UF 16V X7R 0402")
      (fields (field (name "MANUFACTURER PART NUMBER") "GRM155R71C104KA88D") (field (name "TOLERANCE") "10%"))
      (libsource (lib "Altium Content Vault") (part "236180d848d6139a670b325ea6854c9"))
    )
    (comp (ref "C503")
      (value "0.1uF")
      (footprint "FP-GRM15-MFG")
      (description "CAP CER 0.1UF 16V X7R 0402")
      (fields (field (name "MANUFACTURER PART NUMBER") "GRM155R71C104KA88D") (field (name "TOLERANCE") "10%"))
      (libsource (lib "Altium Content Vault") (part "236180d848d6139a670b325ea6854c9"))
    )
    (comp (ref "C504")
      (value "10uF")
      (footprint "FP-C0805C-DG-MFG")
      (description "CAP CER 10UF 10V X5R 0805")
      (fields (field (name "TOLERANCE") "10%") (field (name "MANUFACTURER PART NUMBER") "C0805C106K8PACTU"))
      (libsource (lib "Altium Content Vault") (part "11868f565c42a9108669ba33697ecf6"))
    )
    (comp (ref "C505")
      (value "0.1uF")
      (footprint "FP-GRM15-MFG")
      (description "CAP CER 0.1UF 16V X7R 0402")
      (fields (field (name "MANUFACTURER PART NUMBER") "GRM155R71C104KA88D") (field (name "TOLERANCE") "10%"))
      (libsource (lib "Altium Content Vault") (part "236180d848d6139a670b325ea6854c9"))
    )
    (comp (ref "C506")
      (value "22uF")
      (footprint "FP-GRM21B-0_15-MFG")
      (description "Chip Multilayer Ceramic Capacitors for General Purpose, 0805, 22uF, X5R, 15%, 20%, 6.3V")
      (fields (field (name "VOLTAGE") "6.3V") (field (name "TOLERANCE") "20%"))
      (libsource (lib "Altium Content Vault") (part "b4654b650e69147ec39a6b967a45e02"))
    )
    (comp (ref "C507")
      (value "1500pF")
      (footprint "FP-C0402-BB-MFG")
      (description "CAP CER 1500PF 50V X7R 0402")
      (fields
        (field (name "OCTOPART") "https://octopart.com/c0402c152k5ractu-kemet-125298")
        (field (name "TOLERANCE") "0.1")
      )
      (libsource (lib "Altium Content Vault") (part "b4654b650e69147ec39a6b967a45e02"))
    )
    (comp (ref "C508")
      (value "0.1uF")
      (footprint "FP-GRM15-MFG")
      (description "CAP CER 0.1UF 16V X7R 0402")
      (fields (field (name "MANUFACTURER PART NUMBER") "GRM155R71C104KA88D") (field (name "TOLERANCE") "10%"))
      (libsource (lib "Altium Content Vault") (part "236180d848d6139a670b325ea6854c9"))
    )
    (comp (ref "C509")
      (value "0.1uF")
      (footprint "FP-GRM15-MFG")
      (description "CAP CER 0.1UF 16V X7R 0402")
      (fields (field (name "MANUFACTURER PART NUMBER") "GRM155R71C104KA88D") (field (name "TOLERANCE") "10%"))
      (libsource (lib "Altium Content Vault") (part "236180d848d6139a670b325ea6854c9"))
    )
    (comp (ref "C510")
      (value "0.1uF")
      (footprint "FP-GRM15-MFG")
      (description "CAP CER 0.1UF 16V X7R 0402")
      (fields (field (name "MANUFACTURER PART NUMBER") "GRM155R71C104KA88D") (field (name "TOLERANCE") "10%"))
      (libsource (lib "Altium Content Vault") (part "236180d848d6139a670b325ea6854c9"))
    )
    (comp (ref "C511")
      (value "0.1uF")
      (footprint "FP-GRM15-MFG")
      (description "CAP CER 0.1UF 16V X7R 0402")
      (fields (field (name "MANUFACTURER PART NUMBER") "GRM155R71C104KA88D") (field (name "TOLERANCE") "10%"))
      (libsource (lib "Altium Content Vault") (part "236180d848d6139a670b325ea6854c9"))
    )
    (comp (ref "C512")
      (value "22uF")
      (footprint "FP-GRM21B-0_15-MFG")
      (description "Chip Multilayer Ceramic Capacitors for General Purpose, 0805, 22uF, X5R, 15%, 20%, 6.3V")
      (fields (field (name "VOLTAGE") "6.3V") (field (name "TOLERANCE") "20%"))
      (libsource (lib "Altium Content Vault") (part "b4654b650e69147ec39a6b967a45e02"))
    )
    (comp (ref "C513")
      (value "0.1uF")
      (footprint "FP-GRM15-MFG")
      (description "CAP CER 0.1UF 16V X7R 0402")
      (fields (field (name "MANUFACTURER PART NUMBER") "GRM155R71C104KA88D") (field (name "TOLERANCE") "10%"))
      (libsource (lib "Altium Content Vault") (part "236180d848d6139a670b325ea6854c9"))
    )
    (comp (ref "C514")
      (value "2.2uF")
      (footprint "CAPC1005X55X30NL05T10")
      (fields (field (name "MANUFACTURER") "Kemet") (field (name "PART NUMBER") "C0402C225M9PACTU"))
      (libsource (lib "Altium Content Vault") (part "CAP"))
    )
    (comp (ref "C515")
      (value "2.2uF")
      (footprint "CAPC1005X55X30NL05T10")
      (fields (field (name "MANUFACTURER") "Kemet") (field (name "PART NUMBER") "C0402C225M9PACTU"))
      (libsource (lib "Altium Content Vault") (part "CAP"))
    )
    (comp (ref "C516")
      (value "3000pF")
      (footprint "FP-GRM155-0_05-IPC_B")
      (description "Chip Multilayer Ceramic Capacitors for General Purpose, 0402, 3000pF, U2J, -750ppm/°C, 5%, 10V")
      (fields (field (name "TOLERANCE") "5%"))
      (libsource (lib "Altium Content Vault") (part "02cd4be3c70576c341d710602a673aa"))
    )
    (comp (ref "C517")
      (value "1500pF")
      (footprint "FP-C0402-BB-MFG")
      (description "CAP CER 1500PF 50V X7R 0402")
      (fields
        (field (name "OCTOPART") "https://octopart.com/c0402c152k5ractu-kemet-125298")
        (field (name "TOLERANCE") "0.1")
      )
      (libsource (lib "Altium Content Vault") (part "b4654b650e69147ec39a6b967a45e02"))
    )
    (comp (ref "C518")
      (value "0.1uF")
      (footprint "FP-GRM15-MFG")
      (description "CAP CER 0.1UF 16V X7R 0402")
      (fields (field (name "MANUFACTURER PART NUMBER") "GRM155R71C104KA88D") (field (name "TOLERANCE") "10%"))
      (libsource (lib "Altium Content Vault") (part "236180d848d6139a670b325ea6854c9"))
    )
    (comp (ref "C519")
      (value "0.1uF")
      (footprint "FP-GRM15-MFG")
      (description "CAP CER 0.1UF 16V X7R 0402")
      (fields (field (name "MANUFACTURER PART NUMBER") "GRM155R71C104KA88D") (field (name "TOLERANCE") "10%"))
      (libsource (lib "Altium Content Vault") (part "236180d848d6139a670b325ea6854c9"))
    )
    (comp (ref "C520")
      (value "0.1uF")
      (footprint "FP-GRM15-MFG")
      (description "CAP CER 0.1UF 16V X7R 0402")
      (fields (field (name "MANUFACTURER PART NUMBER") "GRM155R71C104KA88D") (field (name "TOLERANCE") "10%"))
      (libsource (lib "Altium Content Vault") (part "236180d848d6139a670b325ea6854c9"))
    )
    (comp (ref "C521")
      (value "0.1uF")
      (footprint "FP-GRM15-MFG")
      (description "CAP CER 0.1UF 16V X7R 0402")
      (fields (field (name "MANUFACTURER PART NUMBER") "GRM155R71C104KA88D") (field (name "TOLERANCE") "10%"))
      (libsource (lib "Altium Content Vault") (part "236180d848d6139a670b325ea6854c9"))
    )
    (comp (ref "C522")
      (value "0.1uF")
      (footprint "FP-GRM15-MFG")
      (description "CAP CER 0.1UF 16V X7R 0402")
      (fields (field (name "MANUFACTURER PART NUMBER") "GRM155R71C104KA88D") (field (name "TOLERANCE") "10%"))
      (libsource (lib "Altium Content Vault") (part "236180d848d6139a670b325ea6854c9"))
    )
    (comp (ref "C523")
      (value "0.1uF")
      (footprint "FP-GRM15-MFG")
      (description "CAP CER 0.1UF 16V X7R 0402")
      (fields (field (name "MANUFACTURER PART NUMBER") "GRM155R71C104KA88D") (field (name "TOLERANCE") "10%"))
      (libsource (lib "Altium Content Vault") (part "236180d848d6139a670b325ea6854c9"))
    )
    (comp (ref "C524")
      (value "0.1uF")
      (footprint "FP-GRM15-MFG")
      (description "CAP CER 0.1UF 16V X7R 0402")
      (fields (field (name "MANUFACTURER PART NUMBER") "GRM155R71C104KA88D") (field (name "TOLERANCE") "10%"))
      (libsource (lib "Altium Content Vault") (part "236180d848d6139a670b325ea6854c9"))
    )
    (comp (ref "C525")
      (value "0.1uF")
      (footprint "FP-GRM15-MFG")
      (description "CAP CER 0.1UF 16V X7R 0402")
      (fields (field (name "MANUFACTURER PART NUMBER") "GRM155R71C104KA88D") (field (name "TOLERANCE") "10%"))
      (libsource (lib "Altium Content Vault") (part "236180d848d6139a670b325ea6854c9"))
    )
    (comp (ref "C526")
      (value "3000pF")
      (footprint "FP-GRM155-0_05-IPC_B")
      (description "Chip Multilayer Ceramic Capacitors for General Purpose, 0402, 3000pF, U2J, -750ppm/°C, 5%, 10V")
      (fields (field (name "TOLERANCE") "5%"))
      (libsource (lib "Altium Content Vault") (part "02cd4be3c70576c341d710602a673aa"))
    )
    (comp (ref "C527")
      (value "1500pF")
      (footprint "FP-C0402-BB-MFG")
      (description "CAP CER 1500PF 50V X7R 0402")
      (fields
        (field (name "OCTOPART") "https://octopart.com/c0402c152k5ractu-kemet-125298")
        (field (name "TOLERANCE") "0.1")
      )
      (libsource (lib "Altium Content Vault") (part "b4654b650e69147ec39a6b967a45e02"))
    )
    (comp (ref "C528")
      (value "22uF")
      (footprint "FP-GRM21B-0_15-MFG")
      (description "Chip Multilayer Ceramic Capacitors for General Purpose, 0805, 22uF, X5R, 15%, 20%, 6.3V")
      (fields (field (name "VOLTAGE") "6.3V") (field (name "TOLERANCE") "20%"))
      (libsource (lib "Altium Content Vault") (part "b4654b650e69147ec39a6b967a45e02"))
    )
    (comp (ref "C529")
      (value "22uF")
      (footprint "FP-GRM21B-0_15-MFG")
      (description "Chip Multilayer Ceramic Capacitors for General Purpose, 0805, 22uF, X5R, 15%, 20%, 6.3V")
      (fields (field (name "VOLTAGE") "6.3V") (field (name "TOLERANCE") "20%"))
      (libsource (lib "Altium Content Vault") (part "b4654b650e69147ec39a6b967a45e02"))
    )
    (comp (ref "C530")
      (value "22uF")
      (footprint "FP-GRM21B-0_15-MFG")
      (description "Chip Multilayer Ceramic Capacitors for General Purpose, 0805, 22uF, X5R, 15%, 20%, 6.3V")
      (fields (field (name "VOLTAGE") "6.3V") (field (name "TOLERANCE") "20%"))
      (libsource (lib "Altium Content Vault") (part "b4654b650e69147ec39a6b967a45e02"))
    )
    (comp (ref "C531")
      (value "2.2uF")
      (footprint "CAPC1005X55X30NL05T10")
      (fields (field (name "MANUFACTURER") "Kemet") (field (name "PART NUMBER") "C0402C225M9PACTU"))
      (libsource (lib "Altium Content Vault") (part "CAP"))
    )
    (comp (ref "C532")
      (value "2.2uF")
      (footprint "CAPC1005X55X30NL05T10")
      (fields (field (name "MANUFACTURER") "Kemet") (field (name "PART NUMBER") "C0402C225M9PACTU"))
      (libsource (lib "Altium Content Vault") (part "CAP"))
    )
    (comp (ref "C533")
      (value "1uF")
      (footprint "CAPC1005X60X30LL05T10")
      (fields (field (name "PART NUMBER") "C0402C105K8PAC7867") (field (name "MANUFACTURER") "Kemet"))
      (libsource (lib "Altium Content Vault") (part "CAP"))
    )
    (comp (ref "C534")
      (value "10uF")
      (footprint "FP-C0805C-DG-MFG")
      (description "CAP CER 10UF 10V X5R 0805")
      (fields (field (name "TOLERANCE") "10%") (field (name "MANUFACTURER PART NUMBER") "C0805C106K8PACTU"))
      (libsource (lib "Altium Content Vault") (part "11868f565c42a9108669ba33697ecf6"))
    )
    (comp (ref "C535")
      (value "3000pF")
      (footprint "FP-GRM155-0_05-IPC_B")
      (description "Chip Multilayer Ceramic Capacitors for General Purpose, 0402, 3000pF, U2J, -750ppm/°C, 5%, 10V")
      (fields (field (name "TOLERANCE") "5%"))
      (libsource (lib "Altium Content Vault") (part "02cd4be3c70576c341d710602a673aa"))
    )
    (comp (ref "C536")
      (value "4.7uF")
      (footprint "FP-GRM188-0_2-IPC_C")
      (description "Chip Multilayer Ceramic Capacitors for General Purpose, 0603, 4.7uF, X5R, 15%, 10%, 35V")
      (fields (field (name "VOLTAGE") "35V") (field (name "TOLERANCE") "10%"))
      (libsource (lib "Altium Content Vault") (part "11868f565c42a9108669ba33697ecf6"))
    )
    (comp (ref "C537")
      (value "0.47uF")
      (footprint "FP-GRM188-0_1-e0_2_0_5-IPC_B")
      (description "Chip Multilayer Ceramic Capacitors for General Purpose, 0603, 0.47uF, X7R, 15%, 10%, 16V")
      (fields (field (name "VOLTAGE") "16V") (field (name "TOLERANCE") "10%"))
      (libsource (lib "Altium Content Vault") (part "11868f565c42a9108669ba33697ecf6"))
    )
    (comp (ref "C538")
      (value "1uF")
      (footprint "CAPC1005X60X30LL05T10")
      (fields (field (name "PART NUMBER") "C0402C105K8PAC7867") (field (name "MANUFACTURER") "Kemet"))
      (libsource (lib "Altium Content Vault") (part "CAP"))
    )
    (comp (ref "C539")
      (value "10uF")
      (footprint "FP-C0805C-DG-MFG")
      (description "CAP CER 10UF 10V X5R 0805")
      (fields (field (name "TOLERANCE") "10%") (field (name "MANUFACTURER PART NUMBER") "C0805C106K8PACTU"))
      (libsource (lib "Altium Content Vault") (part "11868f565c42a9108669ba33697ecf6"))
    )
    (comp (ref "C540")
      (value "3000pF")
      (footprint "FP-GRM155-0_05-IPC_B")
      (description "Chip Multilayer Ceramic Capacitors for General Purpose, 0402, 3000pF, U2J, -750ppm/°C, 5%, 10V")
      (fields (field (name "TOLERANCE") "5%"))
      (libsource (lib "Altium Content Vault") (part "02cd4be3c70576c341d710602a673aa"))
    )
    (comp (ref "C541")
      (value "4.7uF")
      (footprint "FP-GRM188-0_2-IPC_C")
      (description "Chip Multilayer Ceramic Capacitors for General Purpose, 0603, 4.7uF, X5R, 15%, 10%, 35V")
      (fields (field (name "VOLTAGE") "35V") (field (name "TOLERANCE") "10%"))
      (libsource (lib "Altium Content Vault") (part "11868f565c42a9108669ba33697ecf6"))
    )
    (comp (ref "C542")
      (value "0.47uF")
      (footprint "FP-GRM188-0_1-e0_2_0_5-IPC_B")
      (description "Chip Multilayer Ceramic Capacitors for General Purpose, 0603, 0.47uF, X7R, 15%, 10%, 16V")
      (fields (field (name "VOLTAGE") "16V") (field (name "TOLERANCE") "10%"))
      (libsource (lib "Altium Content Vault") (part "11868f565c42a9108669ba33697ecf6"))
    )
    (comp (ref "C543")
      (value "1uF")
      (footprint "CAPC1005X60X30LL05T10")
      (fields (field (name "PART NUMBER") "C0402C105K8PAC7867") (field (name "MANUFACTURER") "Kemet"))
      (libsource (lib "Altium Content Vault") (part "CAP"))
    )
    (comp (ref "C544")
      (value "10uF")
      (footprint "FP-C0805C-DG-MFG")
      (description "CAP CER 10UF 10V X5R 0805")
      (fields (field (name "TOLERANCE") "10%") (field (name "MANUFACTURER PART NUMBER") "C0805C106K8PACTU"))
      (libsource (lib "Altium Content Vault") (part "11868f565c42a9108669ba33697ecf6"))
    )
    (comp (ref "C545")
      (value "1uF")
      (footprint "CAPC1005X60X30LL05T10")
      (fields (field (name "PART NUMBER") "C0402C105K8PAC7867") (field (name "MANUFACTURER") "Kemet"))
      (libsource (lib "Altium Content Vault") (part "CAP"))
    )
    (comp (ref "C546")
      (value "10uF")
      (footprint "FP-C0805C-DG-MFG")
      (description "CAP CER 10UF 10V X5R 0805")
      (fields (field (name "TOLERANCE") "10%") (field (name "MANUFACTURER PART NUMBER") "C0805C106K8PACTU"))
      (libsource (lib "Altium Content Vault") (part "11868f565c42a9108669ba33697ecf6"))
    )
    (comp (ref "IC30")
      (value "LS1043ASN8QQB")
      (footprint "SamacSys:BGA780C80P28X28_2300X2300X261")
      (description "Integrated Circuit")
      (fields (field (name "MOUSER PART NUMBER") "771-LS1043ASN8QQB"))
      (libsource (lib "SamacSys") (part "LS1043ASN8QQB"))
    )
    (comp (ref "L18")
      (value "220nH")
      (footprint "FP-MPLCG0530-MFG")
      (description "FIXED IND 220NH 14.1A 3.7 MOHM")
      (fields
        (field (name "OCTOPART") "https://octopart.com/mplcg0530lr22-kemet-30531716")
        (field (name "MANUFACTURER") "KEMET")
      )
      (libsource (lib "Altium Content Vault") (part "725321dda6339637d4d059423bc1c3c"))
    )
    (comp (ref "L19")
      (value "220nH")
      (footprint "FP-MPLCG0530-MFG")
      (description "FIXED IND 220NH 14.1A 3.7 MOHM")
      (fields
        (field (name "OCTOPART") "https://octopart.com/mplcg0530lr22-kemet-30531716")
        (field (name "MANUFACTURER") "KEMET")
      )
      (libsource (lib "Altium Content Vault") (part "725321dda6339637d4d059423bc1c3c"))
    )
    (comp (ref "L20")
      (value "220nH")
      (footprint "FP-MPLCG0530-MFG")
      (description "FIXED IND 220NH 14.1A 3.7 MOHM")
      (fields
        (field (name "OCTOPART") "https://octopart.com/mplcg0530lr22-kemet-30531716")
        (field (name "MANUFACTURER") "KEMET")
      )
      (libsource (lib "Altium Content Vault") (part "725321dda6339637d4d059423bc1c3c"))
    )
    (comp (ref "L21")
      (value "220nH")
      (footprint "FP-MPLCG0530-MFG")
      (description "FIXED IND 220NH 14.1A 3.7 MOHM")
      (fields
        (field (name "OCTOPART") "https://octopart.com/mplcg0530lr22-kemet-30531716")
        (field (name "MANUFACTURER") "KEMET")
      )
      (libsource (lib "Altium Content Vault") (part "725321dda6339637d4d059423bc1c3c"))
    )
    (comp (ref "L22")
      (value "220nH")
      (footprint "FP-MPLCG0530-MFG")
      (description "FIXED IND 220NH 14.1A 3.7 MOHM")
      (fields
        (field (name "OCTOPART") "https://octopart.com/mplcg0530lr22-kemet-30531716")
        (field (name "MANUFACTURER") "KEMET")
      )
      (libsource (lib "Altium Content Vault") (part "725321dda6339637d4d059423bc1c3c"))
    )
    (comp (ref "L23")
      (value "220nH")
      (footprint "FP-MPLCG0530-MFG")
      (description "FIXED IND 220NH 14.1A 3.7 MOHM")
      (fields
        (field (name "OCTOPART") "https://octopart.com/mplcg0530lr22-kemet-30531716")
        (field (name "MANUFACTURER") "KEMET")
      )
      (libsource (lib "Altium Content Vault") (part "725321dda6339637d4d059423bc1c3c"))
    )
    (comp (ref "L24")
      (value "220nH")
      (footprint "FP-MPLCG0530-MFG")
      (description "FIXED IND 220NH 14.1A 3.7 MOHM")
      (fields
        (field (name "OCTOPART") "https://octopart.com/mplcg0530lr22-kemet-30531716")
        (field (name "MANUFACTURER") "KEMET")
      )
      (libsource (lib "Altium Content Vault") (part "725321dda6339637d4d059423bc1c3c"))
    )
    (comp (ref "L25")
      (value "220nH")
      (footprint "FP-MPLCG0530-MFG")
      (description "FIXED IND 220NH 14.1A 3.7 MOHM")
      (fields
        (field (name "OCTOPART") "https://octopart.com/mplcg0530lr22-kemet-30531716")
        (field (name "MANUFACTURER") "KEMET")
      )
      (libsource (lib "Altium Content Vault") (part "725321dda6339637d4d059423bc1c3c"))
    )
    (comp (ref "L26")
      (value "220nH")
      (footprint "FP-MPLCG0530-MFG")
      (description "FIXED IND 220NH 14.1A 3.7 MOHM")
      (fields
        (field (name "OCTOPART") "https://octopart.com/mplcg0530lr22-kemet-30531716")
        (field (name "MANUFACTURER") "KEMET")
      )
      (libsource (lib "Altium Content Vault") (part "725321dda6339637d4d059423bc1c3c"))
    )
    (comp (ref "L27")
      (value "220nH")
      (footprint "FP-MPLCG0530-MFG")
      (description "FIXED IND 220NH 14.1A 3.7 MOHM")
      (fields
        (field (name "OCTOPART") "https://octopart.com/mplcg0530lr22-kemet-30531716")
        (field (name "MANUFACTURER") "KEMET")
      )
      (libsource (lib "Altium Content Vault") (part "725321dda6339637d4d059423bc1c3c"))
    )
    (comp (ref "L28")
      (value "220nH")
      (footprint "FP-MPLCG0530-MFG")
      (description "FIXED IND 220NH 14.1A 3.7 MOHM")
      (fields
        (field (name "OCTOPART") "https://octopart.com/mplcg0530lr22-kemet-30531716")
        (field (name "MANUFACTURER") "KEMET")
      )
      (libsource (lib "Altium Content Vault") (part "725321dda6339637d4d059423bc1c3c"))
    )
    (comp (ref "L29")
      (value "220nH")
      (footprint "FP-MPLCG0530-MFG")
      (description "FIXED IND 220NH 14.1A 3.7 MOHM")
      (fields
        (field (name "OCTOPART") "https://octopart.com/mplcg0530lr22-kemet-30531716")
        (field (name "MANUFACTURER") "KEMET")
      )
      (libsource (lib "Altium Content Vault") (part "725321dda6339637d4d059423bc1c3c"))
    )
    (comp (ref "L30")
      (value "220nH")
      (footprint "FP-MPLCG0530-MFG")
      (description "FIXED IND 220NH 14.1A 3.7 MOHM")
      (fields
        (field (name "OCTOPART") "https://octopart.com/mplcg0530lr22-kemet-30531716")
        (field (name "MANUFACTURER") "KEMET")
      )
      (libsource (lib "Altium Content Vault") (part "725321dda6339637d4d059423bc1c3c"))
    )
    (comp (ref "P6")
      (value "5-146280-2")
      (footprint "TECO-5-146280-2_V")
      (fields (field (name "MANUFACTURER") "TE Connectivity"))
      (libsource (lib "") (part "CN-1P-M-R2_1"))
    )
    (comp (ref "P7")
      (value "5-146280-2")
      (footprint "TECO-5-146280-2_V")
      (fields (field (name "MANUFACTURER") "TE Connectivity"))
      (libsource (lib "Altium Content Vault") (part "CN-1P-M-R2"))
    )
    (comp (ref "P8")
      (value "5-146280-2")
      (footprint "TECO-5-146280-2_V")
      (fields (field (name "MANUFACTURER") "TE Connectivity"))
      (libsource (lib "Altium Content Vault") (part "CN-1P-M-R2"))
    )
    (comp (ref "P9")
      (value "5-146280-2")
      (footprint "TECO-5-146280-2_V")
      (fields (field (name "MANUFACTURER") "TE Connectivity"))
      (libsource (lib "Altium Content Vault") (part "CN-1P-M-R2"))
    )
    (comp (ref "R258")
      (value "10")
      (footprint "RESC1005X40X25NL05T05")
      (fields (field (name "PART NUMBER") "CRCW040210R0FKED") (field (name "MANUFACTURER") "Vishay Dale"))
      (libsource (lib "Altium Content Vault") (part "RES"))
    )
    (comp (ref "R259")
      (value "10")
      (footprint "RESC1005X40X25NL05T05")
      (fields (field (name "PART NUMBER") "CRCW040210R0FKED") (field (name "MANUFACTURER") "Vishay Dale"))
      (libsource (lib "Altium Content Vault") (part "RES"))
    )
    (comp (ref "R260")
      (value "330")
      (footprint "FP-CRCW0402-e3-MFG")
      (description "RES Thick Film, 330Ω, 1%, 0.063W, 100ppm/°C, 0402")
      (fields (field (name "TOLERANCE") "1%"))
      (libsource (lib "Altium Content Vault") (part "1029c3af85768c4190bb7ad29bc67b5"))
    )
    (comp (ref "R261")
      (value "330")
      (footprint "FP-CRCW0402-e3-MFG")
      (description "RES Thick Film, 330Ω, 1%, 0.063W, 100ppm/°C, 0402")
      (fields (field (name "TOLERANCE") "1%"))
      (libsource (lib "Altium Content Vault") (part "1029c3af85768c4190bb7ad29bc67b5"))
    )
    (comp (ref "R262")
      (value "330")
      (footprint "FP-CRCW0402-e3-MFG")
      (description "RES Thick Film, 330Ω, 1%, 0.063W, 100ppm/°C, 0402")
      (fields (field (name "TOLERANCE") "1%"))
      (libsource (lib "Altium Content Vault") (part "1029c3af85768c4190bb7ad29bc67b5"))
    )
    (comp (ref "R263")
      (value "330")
      (footprint "FP-CRCW0402-e3-MFG")
      (description "RES Thick Film, 330Ω, 1%, 0.063W, 100ppm/°C, 0402")
      (fields (field (name "TOLERANCE") "1%"))
      (libsource (lib "Altium Content Vault") (part "1029c3af85768c4190bb7ad29bc67b5"))
    )
    (comp (ref "R264")
      (value "330")
      (footprint "FP-CRCW0402-e3-MFG")
      (description "RES Thick Film, 330Ω, 1%, 0.063W, 100ppm/°C, 0402")
      (fields (field (name "TOLERANCE") "1%"))
      (libsource (lib "Altium Content Vault") (part "1029c3af85768c4190bb7ad29bc67b5"))
    )
    (comp (ref "R265")
      (value "5.1")
      (footprint "RESC1005X40X25LL05T05")
      (fields (field (name "PART NUMBER") "CRCW04025R10FKED") (field (name "MANUFACTURER") "Vishay Dale"))
      (libsource (lib "Altium Content Vault") (part "RES"))
    )
    (comp (ref "R266")
      (value "5.1")
      (footprint "RESC1005X40X25LL05T05")
      (fields (field (name "PART NUMBER") "CRCW04025R10FKED") (field (name "MANUFACTURER") "Vishay Dale"))
      (libsource (lib "Altium Content Vault") (part "RES"))
    )
    (comp (ref "R267")
      (value "0.33")
      (footprint "RESC2013X50X40LL20T20")
      (fields (field (name "MANUFACTURER") "Susumu") (field (name "PART NUMBER") "RP2012T-R33-F"))
      (libsource (lib "Altium Content Vault") (part "RES"))
    )
    (comp (ref "R268")
      (value "0.33")
      (footprint "RESC2013X50X40LL20T20")
      (fields (field (name "MANUFACTURER") "Susumu") (field (name "PART NUMBER") "RP2012T-R33-F"))
      (libsource (lib "Altium Content Vault") (part "RES"))
    )
    (comp (ref "R269")
      (value "5.1")
      (footprint "RESC1005X40X25LL05T05")
      (fields (field (name "PART NUMBER") "CRCW04025R10FKED") (field (name "MANUFACTURER") "Vishay Dale"))
      (libsource (lib "Altium Content Vault") (part "RES"))
    )
    (comp (ref "R270")
      (value "5.1")
      (footprint "RESC1005X40X25LL05T05")
      (fields (field (name "PART NUMBER") "CRCW04025R10FKED") (field (name "MANUFACTURER") "Vishay Dale"))
      (libsource (lib "Altium Content Vault") (part "RES"))
    )
  )
  (nets
    (net (code "1") (name "+1V8") (class "Default")
      (node (ref "C455") (pin "2") (pinfunction "2_2") (pintype "passive"))
      (node (ref "C456") (pin "2") (pinfunction "2_2") (pintype "passive"))
      (node (ref "C457") (pin "2") (pinfunction "2_2") (pintype "passive"))
      (node (ref "C458") (pin "2") (pinfunction "2_2") (pintype "passive"))
      (node (ref "C459") (pin "2") (pinfunction "2_2") (pintype "passive"))
      (node (ref "C460") (pin "2") (pinfunction "2_2") (pintype "passive"))
      (node (ref "C461") (pin "2") (pinfunction "2_2") (pintype "passive"))
      (node (ref "C462") (pin "1") (pinfunction "1_1") (pintype "passive"))
      (node (ref "C463") (pin "1") (pinfunction "1_1") (pintype "passive"))
      (node (ref "C503") (pin "2") (pinfunction "2_2") (pintype "passive"))
      (node (ref "C504") (pin "1") (pinfunction "1_1") (pintype "passive"))
      (node (ref "C511") (pin "2") (pinfunction "2_2") (pintype "passive"))
      (node (ref "C512") (pin "1") (pinfunction "1_1") (pintype "passive"))
      (node (ref "IC30") (pin "J12") (pinfunction "OVDD1_J12") (pintype "passive"))
      (node (ref "IC30") (pin "J13") (pinfunction "OVDD2_J13") (pintype "passive"))
      (node (ref "IC30") (pin "J14") (pinfunction "OVDD3_J14") (pintype "passive"))
      (node (ref "IC30") (pin "J15") (pinfunction "OVDD4_J15") (pintype "passive"))
      (node (ref "IC30") (pin "J16") (pinfunction "OVDD5_J16") (pintype "passive"))
      (node (ref "IC30") (pin "J17") (pinfunction "OVDD6_J17") (pintype "passive"))
      (node (ref "IC30") (pin "N7") (pinfunction "OVDD7_N7") (pintype "passive"))
      (node (ref "IC30") (pin "T6") (pinfunction "TH_VDD_T6") (pintype "passive"))
      (node (ref "L22") (pin "2") (pinfunction "2_2") (pintype "passive"))
      (node (ref "P7") (pin "1") (pinfunction "1_1") (pintype "passive"))
      (node (ref "P8") (pin "2") (pinfunction "2_2") (pintype "passive"))
      (node (ref "R261") (pin "2") (pinfunction "2_2") (pintype "passive"))
      (node (ref "R265") (pin "1") (pinfunction "1_1") (pintype "passive"))
      (node (ref "R266") (pin "1") (pinfunction "1_1") (pintype "passive"))
      (node (ref "R269") (pin "1") (pinfunction "1_1") (pintype "passive"))
      (node (ref "R270") (pin "1") (pinfunction "1_1") (pintype "passive"))
    )
    (net (code "2") (name "+2V5") (class "Default")
      (node (ref "L21") (pin "2") (pinfunction "2_2") (pintype "passive"))
      (node (ref "L24") (pin "1") (pinfunction "1_1") (pintype "passive"))
    )
    (net (code "3") (name "+3V3") (class "Default")
      (node (ref "C485") (pin "2") (pinfunction "2_2") (pintype "passive"))
      (node (ref "C486") (pin "2") (pinfunction "2_2") (pintype "passive"))
      (node (ref "C487") (pin "1") (pinfunction "1_1") (pintype "passive"))
      (node (ref "IC30") (pin "K8") (pinfunction "DVDD1_K8") (pintype "passive"))
      (node (ref "IC30") (pin "L8") (pinfunction "DVDD2_L8") (pintype "passive"))
      (node (ref "L20") (pin "2") (pinfunction "2_2") (pintype "passive"))
      (node (ref "L23") (pin "2") (pinfunction "2_2") (pintype "passive"))
    )
    (net (code "4") (name "+CPU_VDD") (class "Default")
      (node (ref "C395") (pin "1") (pinfunction "1_1") (pintype "passive"))
      (node (ref "C396") (pin "1") (pinfunction "1_1") (pintype "passive"))
      (node (ref "C397") (pin "1") (pinfunction "1_1") (pintype "passive"))
      (node (ref "C398") (pin "1") (pinfunction "1_1") (pintype "passive"))
      (node (ref "C399") (pin "1") (pinfunction "1_1") (pintype "passive"))
      (node (ref "C400") (pin "1") (pinfunction "1_1") (pintype "passive"))
      (node (ref "C401") (pin "1") (pinfunction "1_1") (pintype "passive"))
      (node (ref "C402") (pin "1") (pinfunction "1_1") (pintype "passive"))
      (node (ref "C403") (pin "1") (pinfunction "1_1") (pintype "passive"))
      (node (ref "C404") (pin "2") (pinfunction "2_2") (pintype "passive"))
      (node (ref "C405") (pin "2") (pinfunction "2_2") (pintype "passive"))
      (node (ref "C406") (pin "2") (pinfunction "2_2") (pintype "passive"))
      (node (ref "C407") (pin "2") (pinfunction "2_2") (pintype "passive"))
      (node (ref "C408") (pin "2") (pinfunction "2_2") (pintype "passive"))
      (node (ref "C409") (pin "2") (pinfunction "2_2") (pintype "passive"))
      (node (ref "C410") (pin "2") (pinfunction "2_2") (pintype "passive"))
      (node (ref "C411") (pin "2") (pinfunction "2_2") (pintype "passive"))
      (node (ref "C412") (pin "2") (pinfunction "2_2") (pintype "passive"))
      (node (ref "C413") (pin "2") (pinfunction "2_2") (pintype "passive"))
      (node (ref "C414") (pin "1") (pinfunction "1_1") (pintype "passive"))
      (node (ref "C415") (pin "1") (pinfunction "1_1") (pintype "passive"))
      (node (ref "C416") (pin "1") (pinfunction "1_1") (pintype "passive"))
      (node (ref "C421") (pin "2") (pinfunction "2_2") (pintype "passive"))
      (node (ref "C422") (pin "2") (pinfunction "2_2") (pintype "passive"))
      (node (ref "C423") (pin "2") (pinfunction "2_2") (pintype "passive"))
      (node (ref "C424") (pin "2") (pinfunction "2_2") (pintype "passive"))
      (node (ref "C425") (pin "2") (pinfunction "2_2") (pintype "passive"))
      (node (ref "C426") (pin "2") (pinfunction "2_2") (pintype "passive"))
      (node (ref "C427") (pin "2") (pinfunction "2_2") (pintype "passive"))
      (node (ref "C428") (pin "2") (pinfunction "2_2") (pintype "passive"))
      (node (ref "C429") (pin "2") (pinfunction "2_2") (pintype "passive"))
      (node (ref "C430") (pin "2") (pinfunction "2_2") (pintype "passive"))
      (node (ref "C431") (pin "1") (pinfunction "1_1") (pintype "passive"))
      (node (ref "C432") (pin "1") (pinfunction "1_1") (pintype "passive"))
      (node (ref "C433") (pin "1") (pinfunction "1_1") (pintype "passive"))
      (node (ref "C438") (pin "2") (pinfunction "2_2") (pintype "passive"))
      (node (ref "C439") (pin "2") (pinfunction "2_2") (pintype "passive"))
      (node (ref "C440") (pin "2") (pinfunction "2_2") (pintype "passive"))
      (node (ref "C441") (pin "2") (pinfunction "2_2") (pintype "passive"))
      (node (ref "C442") (pin "2") (pinfunction "2_2") (pintype "passive"))
      (node (ref "C443") (pin "2") (pinfunction "2_2") (pintype "passive"))
      (node (ref "C444") (pin "2") (pinfunction "2_2") (pintype "passive"))
      (node (ref "C445") (pin "2") (pinfunction "2_2") (pintype "passive"))
      (node (ref "C446") (pin "2") (pinfunction "2_2") (pintype "passive"))
      (node (ref "C447") (pin "2") (pinfunction "2_2") (pintype "passive"))
      (node (ref "C448") (pin "1") (pinfunction "1_1") (pintype "passive"))
      (node (ref "C449") (pin "1") (pinfunction "1_1") (pintype "passive"))
      (node (ref "C450") (pin "1") (pinfunction "1_1") (pintype "passive"))
      (node (ref "IC30") (pin "K13") (pinfunction "VDD01_K13") (pintype "passive"))
      (node (ref "IC30") (pin "K15") (pinfunction "VDD02_K15") (pintype "passive"))
      (node (ref "IC30") (pin "K17") (pinfunction "VDD03_K17") (pintype "passive"))
      (node (ref "IC30") (pin "L10") (pinfunction "VDD04_L10") (pintype "passive"))
      (node (ref "IC30") (pin "L12") (pinfunction "VDD05_L12") (pintype "passive"))
      (node (ref "IC30") (pin "L14") (pinfunction "VDD06_L14") (pintype "passive"))
      (node (ref "IC30") (pin "L16") (pinfunction "VDD07_L16") (pintype "passive"))
      (node (ref "IC30") (pin "M11") (pinfunction "VDD09_M11") (pintype "passive"))
      (node (ref "IC30") (pin "M13") (pinfunction "VDD10_M13") (pintype "passive"))
      (node (ref "IC30") (pin "M15") (pinfunction "VDD11_M15") (pintype "passive"))
      (node (ref "IC30") (pin "M17") (pinfunction "VDD12_M17") (pintype "passive"))
      (node (ref "IC30") (pin "M9") (pinfunction "VDD08_M9") (pintype "passive"))
      (node (ref "IC30") (pin "N10") (pinfunction "VDD14_N10") (pintype "passive"))
      (node (ref "IC30") (pin "N12") (pinfunction "VDD15_N12") (pintype "passive"))
      (node (ref "IC30") (pin "N14") (pinfunction "VDD16_N14") (pintype "passive"))
      (node (ref "IC30") (pin "N16") (pinfunction "VDD17_N16") (pintype "passive"))
      (node (ref "IC30") (pin "N8") (pinfunction "VDD13_N8") (pintype "passive"))
      (node (ref "IC30") (pin "P11") (pinfunction "VDD19_P11") (pintype "passive"))
      (node (ref "IC30") (pin "P13") (pinfunction "VDD20_P13") (pintype "passive"))
      (node (ref "IC30") (pin "P15") (pinfunction "VDD21_P15") (pintype "passive"))
      (node (ref "IC30") (pin "P17") (pinfunction "VDD22_P17") (pintype "passive"))
      (node (ref "IC30") (pin "P9") (pinfunction "VDD18_P9") (pintype "passive"))
      (node (ref "IC30") (pin "R10") (pinfunction "VDD24_R10") (pintype "passive"))
      (node (ref "IC30") (pin "R12") (pinfunction "VDD25_R12") (pintype "passive"))
      (node (ref "IC30") (pin "R14") (pinfunction "VDD26_R14") (pintype "passive"))
      (node (ref "IC30") (pin "R16") (pinfunction "VDD27_R16") (pintype "passive"))
      (node (ref "IC30") (pin "R18") (pinfunction "VDD28_R18") (pintype "passive"))
      (node (ref "IC30") (pin "R8") (pinfunction "VDD23_R8") (pintype "passive"))
      (node (ref "IC30") (pin "T11") (pinfunction "VDD30_T11") (pintype "passive"))
      (node (ref "IC30") (pin "T13") (pinfunction "VDD31_T13") (pintype "passive"))
      (node (ref "IC30") (pin "T9") (pinfunction "VDD29_T9") (pintype "passive"))
      (node (ref "IC30") (pin "U10") (pinfunction "VDD33_U10") (pintype "passive"))
      (node (ref "IC30") (pin "U8") (pinfunction "VDD32_U8") (pintype "passive"))
      (node (ref "L18") (pin "2") (pinfunction "2_2") (pintype "passive"))
      (node (ref "L19") (pin "2") (pinfunction "2_2") (pintype "passive"))
      (node (ref "L25") (pin "1") (pinfunction "1_1") (pintype "passive"))
      (node (ref "L27") (pin "1") (pinfunction "1_1") (pintype "passive"))
      (node (ref "P6") (pin "2") (pinfunction "2_2") (pintype "passive"))
      (node (ref "P9") (pin "2") (pinfunction "2_2") (pintype "passive"))
    )
    (net (code "5") (name "+GVDD") (class "Default")
      (node (ref "IC30") (pin "AA20") (pinfunction "G1VDD18_AA20") (pintype "passive"))
      (node (ref "IC30") (pin "AB22") (pinfunction "G1VDD19_AB22") (pintype "passive"))
      (node (ref "IC30") (pin "AB24") (pinfunction "G1VDD20_AB24") (pintype "passive"))
      (node (ref "IC30") (pin "AD22") (pinfunction "G1VDD21_AD22") (pintype "passive"))
      (node (ref "IC30") (pin "AD24") (pinfunction "G1VDD23_AD24") (pintype "passive"))
      (node (ref "IC30") (pin "AD25") (pinfunction "G1VDD22_AD25") (pintype "passive"))
      (node (ref "IC30") (pin "J18") (pinfunction "G1VDD01_J18") (pintype "passive"))
      (node (ref "IC30") (pin "K18") (pinfunction "G1VDD02_K18") (pintype "passive"))
      (node (ref "IC30") (pin "K20") (pinfunction "G1VDD03_K20") (pintype "passive"))
      (node (ref "IC30") (pin "L18") (pinfunction "G1VDD04_L18") (pintype "passive"))
      (node (ref "IC30") (pin "M18") (pinfunction "G1VDD05_M18") (pintype "passive"))
      (node (ref "IC30") (pin "M20") (pinfunction "G1VDD06_M20") (pintype "passive"))
      (node (ref "IC30") (pin "N18") (pinfunction "G1VDD07_N18") (pintype "passive"))
      (node (ref "IC30") (pin "P18") (pinfunction "G1VDD08_P18") (pintype "passive"))
      (node (ref "IC30") (pin "P20") (pinfunction "G1VDD09_P20") (pintype "passive"))
      (node (ref "IC30") (pin "R21") (pinfunction "G1VDD10_R21") (pintype "passive"))
      (node (ref "IC30") (pin "R23") (pinfunction "G1VDD11_R23") (pintype "passive"))
      (node (ref "IC30") (pin "T22") (pinfunction "G1VDD12_T22") (pintype "passive"))
      (node (ref "IC30") (pin "T24") (pinfunction "G1VDD13_T24") (pintype "passive"))
      (node (ref "IC30") (pin "V22") (pinfunction "G1VDD14_V22") (pintype "passive"))
      (node (ref "IC30") (pin "V24") (pinfunction "G1VDD15_V24") (pintype "passive"))
      (node (ref "IC30") (pin "Y22") (pinfunction "G1VDD16_Y22") (pintype "passive"))
      (node (ref "IC30") (pin "Y24") (pinfunction "G1VDD17_Y24") (pintype "passive"))
    )
    (net (code "6") (name "+GVVD") (class "Default")
      (node (ref "C464") (pin "1") (pinfunction "1_1") (pintype "passive"))
      (node (ref "C465") (pin "1") (pinfunction "1_1") (pintype "passive"))
      (node (ref "C466") (pin "1") (pinfunction "1_1") (pintype "passive"))
      (node (ref "C467") (pin "1") (pinfunction "1_1") (pintype "passive"))
      (node (ref "C468") (pin "1") (pinfunction "1_1") (pintype "passive"))
      (node (ref "C469") (pin "1") (pinfunction "1_1") (pintype "passive"))
      (node (ref "C470") (pin "1") (pinfunction "1_1") (pintype "passive"))
      (node (ref "C471") (pin "1") (pinfunction "1_1") (pintype "passive"))
      (node (ref "C472") (pin "1") (pinfunction "1_1") (pintype "passive"))
      (node (ref "C473") (pin "2") (pinfunction "2_2") (pintype "passive"))
      (node (ref "C474") (pin "2") (pinfunction "2_2") (pintype "passive"))
      (node (ref "C475") (pin "2") (pinfunction "2_2") (pintype "passive"))
      (node (ref "C476") (pin "2") (pinfunction "2_2") (pintype "passive"))
      (node (ref "C477") (pin "2") (pinfunction "2_2") (pintype "passive"))
      (node (ref "C478") (pin "2") (pinfunction "2_2") (pintype "passive"))
      (node (ref "C479") (pin "2") (pinfunction "2_2") (pintype "passive"))
      (node (ref "C480") (pin "2") (pinfunction "2_2") (pintype "passive"))
      (node (ref "C481") (pin "2") (pinfunction "2_2") (pintype "passive"))
      (node (ref "C482") (pin "2") (pinfunction "2_2") (pintype "passive"))
      (node (ref "C483") (pin "2") (pinfunction "2_2") (pintype "passive"))
      (node (ref "C484") (pin "2") (pinfunction "2_2") (pintype "passive"))
      (node (ref "C490") (pin "2") (pinfunction "2_2") (pintype "passive"))
      (node (ref "C491") (pin "2") (pinfunction "2_2") (pintype "passive"))
      (node (ref "C492") (pin "2") (pinfunction "2_2") (pintype "passive"))
      (node (ref "C493") (pin "2") (pinfunction "2_2") (pintype "passive"))
      (node (ref "C494") (pin "2") (pinfunction "2_2") (pintype "passive"))
      (node (ref "C495") (pin "2") (pinfunction "2_2") (pintype "passive"))
      (node (ref "C496") (pin "2") (pinfunction "2_2") (pintype "passive"))
      (node (ref "C497") (pin "2") (pinfunction "2_2") (pintype "passive"))
      (node (ref "C498") (pin "2") (pinfunction "2_2") (pintype "passive"))
      (node (ref "C499") (pin "2") (pinfunction "2_2") (pintype "passive"))
      (node (ref "C500") (pin "2") (pinfunction "2_2") (pintype "passive"))
    )
    (net (code "7") (name "/AVDD_CGA1") (class "Default")
      (node (ref "C533") (pin "2") (pinfunction "2_2") (pintype "passive"))
      (node (ref "C534") (pin "1") (pinfunction "1_1") (pintype "passive"))
      (node (ref "IC30") (pin "G12") (pinfunction "AVDD_CGA1_G12") (pintype "passive"))
      (node (ref "R265") (pin "2") (pinfunction "2_2") (pintype "passive"))
    )
    (net (code "8") (name "/AVDD_CGA2") (class "Default")
      (node (ref "C538") (pin "2") (pinfunction "2_2") (pintype "passive"))
      (node (ref "C539") (pin "1") (pinfunction "1_1") (pintype "passive"))
      (node (ref "IC30") (pin "G11") (pinfunction "AVDD_CGA2_G11") (pintype "passive"))
      (node (ref "R266") (pin "2") (pinfunction "2_2") (pintype "passive"))
    )
    (net (code "9") (name "/AVDD_DDR1") (class "Default")
      (node (ref "C545") (pin "2") (pinfunction "2_2") (pintype "passive"))
      (node (ref "C546") (pin "1") (pinfunction "1_1") (pintype "passive"))
      (node (ref "IC30") (pin "T19") (pinfunction "AVDD_D1_T19") (pintype "passive"))
      (node (ref "R270") (pin "2") (pinfunction "2_2") (pintype "passive"))
    )
    (net (code "10") (name "/AVDD_PLAT") (class "Default")
      (node (ref "C543") (pin "2") (pinfunction "2_2") (pintype "passive"))
      (node (ref "C544") (pin "1") (pinfunction "1_1") (pintype "passive"))
      (node (ref "IC30") (pin "G13") (pinfunction "AVDD_PLAT_G13") (pintype "passive"))
      (node (ref "R269") (pin "2") (pinfunction "2_2") (pintype "passive"))
    )
    (net (code "11") (name "/AVDD_SRDS1_PLL1") (class "Default")
      (node (ref "C535") (pin "1") (pinfunction "1_1") (pintype "passive"))
      (node (ref "C536") (pin "1") (pinfunction "1_1") (pintype "passive"))
      (node (ref "C537") (pin "1") (pinfunction "1_1") (pintype "passive"))
      (node (ref "IC30") (pin "W12") (pinfunction "AVDD_SD1_PLL1_W12") (pintype "passive"))
      (node (ref "R267") (pin "2") (pinfunction "2_2") (pintype "passive"))
    )
    (net (code "12") (name "/AVDD_SRDS1_PLL2") (class "Default")
      (node (ref "C540") (pin "1") (pinfunction "1_1") (pintype "passive"))
      (node (ref "C541") (pin "1") (pinfunction "1_1") (pintype "passive"))
      (node (ref "C542") (pin "1") (pinfunction "1_1") (pintype "passive"))
      (node (ref "IC30") (pin "V19") (pinfunction "AVDD_SD1_PLL2_V19") (pintype "passive"))
      (node (ref "R268") (pin "2") (pinfunction "2_2") (pintype "passive"))
    )
    (net (code "13") (name "/CPU_GND_SENSE") (class "Default")
      (node (ref "R259") (pin "2") (pinfunction "2_2") (pintype "passive"))
    )
    (net (code "14") (name "/CPU_VDD_SENSE") (class "Default")
      (node (ref "R258") (pin "2") (pinfunction "2_2") (pintype "passive"))
    )
    (net (code "15") (name "/PWR_PROG_MTR") (class "Default")
      (node (ref "C501") (pin "2") (pinfunction "2_2") (pintype "passive"))
      (node (ref "IC30") (pin "G14") (pinfunction "PROG_MTR_G14") (pintype "passive"))
      (node (ref "P8") (pin "1") (pinfunction "1_1") (pintype "passive"))
      (node (ref "R262") (pin "2") (pinfunction "2_2") (pintype "passive"))
    )
    (net (code "16") (name "/PWR_PROG_SFP") (class "Default")
      (node (ref "C502") (pin "2") (pinfunction "2_2") (pintype "passive"))
      (node (ref "IC30") (pin "F14") (pinfunction "TA_PROG_SFP_F14") (pintype "passive"))
      (node (ref "P7") (pin "2") (pinfunction "2_2") (pintype "passive"))
      (node (ref "R263") (pin "2") (pinfunction "2_2") (pintype "passive"))
    )
    (net (code "17") (name "EVVD") (class "Default")
      (node (ref "C488") (pin "2") (pinfunction "2_2") (pintype "passive"))
      (node (ref "C489") (pin "1") (pinfunction "1_1") (pintype "passive"))
      (node (ref "IC30") (pin "M8") (pinfunction "EVDD_M8") (pintype "passive"))
      (node (ref "L22") (pin "1") (pinfunction "1_1") (pintype "passive"))
      (node (ref "L23") (pin "1") (pinfunction "1_1") (pintype "passive"))
    )
    (net (code "18") (name "GND") (class "Default")
      (node (ref "C395") (pin "2") (pinfunction "2_2") (pintype "passive"))
      (node (ref "C396") (pin "2") (pinfunction "2_2") (pintype "passive"))
      (node (ref "C397") (pin "2") (pinfunction "2_2") (pintype "passive"))
      (node (ref "C398") (pin "2") (pinfunction "2_2") (pintype "passive"))
      (node (ref "C399") (pin "2") (pinfunction "2_2") (pintype "passive"))
      (node (ref "C400") (pin "2") (pinfunction "2_2") (pintype "passive"))
      (node (ref "C401") (pin "2") (pinfunction "2_2") (pintype "passive"))
      (node (ref "C402") (pin "2") (pinfunction "2_2") (pintype "passive"))
      (node (ref "C403") (pin "2") (pinfunction "2_2") (pintype "passive"))
      (node (ref "C404") (pin "1") (pinfunction "1_1") (pintype "passive"))
      (node (ref "C405") (pin "1") (pinfunction "1_1") (pintype "passive"))
      (node (ref "C406") (pin "1") (pinfunction "1_1") (pintype "passive"))
      (node (ref "C407") (pin "1") (pinfunction "1_1") (pintype "passive"))
      (node (ref "C408") (pin "1") (pinfunction "1_1") (pintype "passive"))
      (node (ref "C409") (pin "1") (pinfunction "1_1") (pintype "passive"))
      (node (ref "C410") (pin "1") (pinfunction "1_1") (pintype "passive"))
      (node (ref "C411") (pin "1") (pinfunction "1_1") (pintype "passive"))
      (node (ref "C412") (pin "1") (pinfunction "1_1") (pintype "passive"))
      (node (ref "C413") (pin "1") (pinfunction "1_1") (pintype "passive"))
      (node (ref "C414") (pin "2") (pinfunction "2_2") (pintype "passive"))
      (node (ref "C415") (pin "2") (pinfunction "2_2") (pintype "passive"))
      (node (ref "C416") (pin "2") (pinfunction "2_2") (pintype "passive"))
      (node (ref "C417") (pin "1") (pinfunction "1_1") (pintype "passive"))
      (node (ref "C418") (pin "1") (pinfunction "1_1") (pintype "passive"))
      (node (ref "C419") (pin "2") (pinfunction "2_2") (pintype "passive"))
      (node (ref "C420") (pin "1") (pinfunction "1_1") (pintype "passive"))
      (node (ref "C421") (pin "1") (pinfunction "1_1") (pintype "passive"))
      (node (ref "C422") (pin "1") (pinfunction "1_1") (pintype "passive"))
      (node (ref "C423") (pin "1") (pinfunction "1_1") (pintype "passive"))
      (node (ref "C424") (pin "1") (pinfunction "1_1") (pintype "passive"))
      (node (ref "C425") (pin "1") (pinfunction "1_1") (pintype "passive"))
      (node (ref "C426") (pin "1") (pinfunction "1_1") (pintype "passive"))
      (node (ref "C427") (pin "1") (pinfunction "1_1") (pintype "passive"))
      (node (ref "C428") (pin "1") (pinfunction "1_1") (pintype "passive"))
      (node (ref "C429") (pin "1") (pinfunction "1_1") (pintype "passive"))
      (node (ref "C430") (pin "1") (pinfunction "1_1") (pintype "passive"))
      (node (ref "C431") (pin "2") (pinfunction "2_2") (pintype "passive"))
      (node (ref "C432") (pin "2") (pinfunction "2_2") (pintype "passive"))
      (node (ref "C433") (pin "2") (pinfunction "2_2") (pintype "passive"))
      (node (ref "C434") (pin "1") (pinfunction "1_1") (pintype "passive"))
      (node (ref "C435") (pin "1") (pinfunction "1_1") (pintype "passive"))
      (node (ref "C436") (pin "2") (pinfunction "2_2") (pintype "passive"))
      (node (ref "C437") (pin "1") (pinfunction "1_1") (pintype "passive"))
      (node (ref "C438") (pin "1") (pinfunction "1_1") (pintype "passive"))
      (node (ref "C439") (pin "1") (pinfunction "1_1") (pintype "passive"))
      (node (ref "C440") (pin "1") (pinfunction "1_1") (pintype "passive"))
      (node (ref "C441") (pin "1") (pinfunction "1_1") (pintype "passive"))
      (node (ref "C442") (pin "1") (pinfunction "1_1") (pintype "passive"))
      (node (ref "C443") (pin "1") (pinfunction "1_1") (pintype "passive"))
      (node (ref "C444") (pin "1") (pinfunction "1_1") (pintype "passive"))
      (node (ref "C445") (pin "1") (pinfunction "1_1") (pintype "passive"))
      (node (ref "C446") (pin "1") (pinfunction "1_1") (pintype "passive"))
      (node (ref "C447") (pin "1") (pinfunction "1_1") (pintype "passive"))
      (node (ref "C448") (pin "2") (pinfunction "2_2") (pintype "passive"))
      (node (ref "C449") (pin "2") (pinfunction "2_2") (pintype "passive"))
      (node (ref "C450") (pin "2") (pinfunction "2_2") (pintype "passive"))
      (node (ref "C451") (pin "2") (pinfunction "2_2") (pintype "passive"))
      (node (ref "C452") (pin "1") (pinfunction "1_1") (pintype "passive"))
      (node (ref "C453") (pin "1") (pinfunction "1_1") (pintype "passive"))
      (node (ref "C454") (pin "2") (pinfunction "2_2") (pintype "passive"))
      (node (ref "C455") (pin "1") (pinfunction "1_1") (pintype "passive"))
      (node (ref "C456") (pin "1") (pinfunction "1_1") (pintype "passive"))
      (node (ref "C457") (pin "1") (pinfunction "1_1") (pintype "passive"))
      (node (ref "C458") (pin "1") (pinfunction "1_1") (pintype "passive"))
      (node (ref "C459") (pin "1") (pinfunction "1_1") (pintype "passive"))
      (node (ref "C460") (pin "1") (pinfunction "1_1") (pintype "passive"))
      (node (ref "C461") (pin "1") (pinfunction "1_1") (pintype "passive"))
      (node (ref "C462") (pin "2") (pinfunction "2_2") (pintype "passive"))
      (node (ref "C463") (pin "2") (pinfunction "2_2") (pintype "passive"))
      (node (ref "C464") (pin "2") (pinfunction "2_2") (pintype "passive"))
      (node (ref "C465") (pin "2") (pinfunction "2_2") (pintype "passive"))
      (node (ref "C466") (pin "2") (pinfunction "2_2") (pintype "passive"))
      (node (ref "C467") (pin "2") (pinfunction "2_2") (pintype "passive"))
      (node (ref "C468") (pin "2") (pinfunction "2_2") (pintype "passive"))
      (node (ref "C469") (pin "2") (pinfunction "2_2") (pintype "passive"))
      (node (ref "C470") (pin "2") (pinfunction "2_2") (pintype "passive"))
      (node (ref "C471") (pin "2") (pinfunction "2_2") (pintype "passive"))
      (node (ref "C472") (pin "2") (pinfunction "2_2") (pintype "passive"))
      (node (ref "C473") (pin "1") (pinfunction "1_1") (pintype "passive"))
      (node (ref "C474") (pin "1") (pinfunction "1_1") (pintype "passive"))
      (node (ref "C475") (pin "1") (pinfunction "1_1") (pintype "passive"))
      (node (ref "C476") (pin "1") (pinfunction "1_1") (pintype "passive"))
      (node (ref "C477") (pin "1") (pinfunction "1_1") (pintype "passive"))
      (node (ref "C478") (pin "1") (pinfunction "1_1") (pintype "passive"))
      (node (ref "C479") (pin "1") (pinfunction "1_1") (pintype "passive"))
      (node (ref "C480") (pin "1") (pinfunction "1_1") (pintype "passive"))
      (node (ref "C481") (pin "1") (pinfunction "1_1") (pintype "passive"))
      (node (ref "C482") (pin "1") (pinfunction "1_1") (pintype "passive"))
      (node (ref "C483") (pin "1") (pinfunction "1_1") (pintype "passive"))
      (node (ref "C484") (pin "1") (pinfunction "1_1") (pintype "passive"))
      (node (ref "C485") (pin "1") (pinfunction "1_1") (pintype "passive"))
      (node (ref "C486") (pin "1") (pinfunction "1_1") (pintype "passive"))
      (node (ref "C487") (pin "2") (pinfunction "2_2") (pintype "passive"))
      (node (ref "C488") (pin "1") (pinfunction "1_1") (pintype "passive"))
      (node (ref "C489") (pin "2") (pinfunction "2_2") (pintype "passive"))
      (node (ref "C490") (pin "1") (pinfunction "1_1") (pintype "passive"))
      (node (ref "C491") (pin "1") (pinfunction "1_1") (pintype "passive"))
      (node (ref "C492") (pin "1") (pinfunction "1_1") (pintype "passive"))
      (node (ref "C493") (pin "1") (pinfunction "1_1") (pintype "passive"))
      (node (ref "C494") (pin "1") (pinfunction "1_1") (pintype "passive"))
      (node (ref "C495") (pin "1") (pinfunction "1_1") (pintype "passive"))
      (node (ref "C496") (pin "1") (pinfunction "1_1") (pintype "passive"))
      (node (ref "C497") (pin "1") (pinfunction "1_1") (pintype "passive"))
      (node (ref "C498") (pin "1") (pinfunction "1_1") (pintype "passive"))
      (node (ref "C499") (pin "1") (pinfunction "1_1") (pintype "passive"))
      (node (ref "C500") (pin "1") (pinfunction "1_1") (pintype "passive"))
      (node (ref "C501") (pin "1") (pinfunction "1_1") (pintype "passive"))
      (node (ref "C502") (pin "1") (pinfunction "1_1") (pintype "passive"))
      (node (ref "C503") (pin "1") (pinfunction "1_1") (pintype "passive"))
      (node (ref "C504") (pin "2") (pinfunction "2_2") (pintype "passive"))
      (node (ref "C506") (pin "2") (pinfunction "2_2") (pintype "passive"))
      (node (ref "C507") (pin "2") (pinfunction "2_2") (pintype "passive"))
      (node (ref "C508") (pin "1") (pinfunction "1_1") (pintype "passive"))
      (node (ref "C509") (pin "1") (pinfunction "1_1") (pintype "passive"))
      (node (ref "C510") (pin "1") (pinfunction "1_1") (pintype "passive"))
      (node (ref "C514") (pin "1") (pinfunction "1_1") (pintype "passive"))
      (node (ref "C515") (pin "1") (pinfunction "1_1") (pintype "passive"))
      (node (ref "C516") (pin "2") (pinfunction "2_2") (pintype "passive"))
      (node (ref "C517") (pin "2") (pinfunction "2_2") (pintype "passive"))
      (node (ref "C518") (pin "1") (pinfunction "1_1") (pintype "passive"))
      (node (ref "C519") (pin "1") (pinfunction "1_1") (pintype "passive"))
      (node (ref "C520") (pin "1") (pinfunction "1_1") (pintype "passive"))
      (node (ref "C521") (pin "1") (pinfunction "1_1") (pintype "passive"))
      (node (ref "C522") (pin "1") (pinfunction "1_1") (pintype "passive"))
      (node (ref "C523") (pin "1") (pinfunction "1_1") (pintype "passive"))
      (node (ref "C524") (pin "1") (pinfunction "1_1") (pintype "passive"))
      (node (ref "C525") (pin "1") (pinfunction "1_1") (pintype "passive"))
      (node (ref "C526") (pin "2") (pinfunction "2_2") (pintype "passive"))
      (node (ref "C527") (pin "2") (pinfunction "2_2") (pintype "passive"))
      (node (ref "C528") (pin "2") (pinfunction "2_2") (pintype "passive"))
      (node (ref "C529") (pin "2") (pinfunction "2_2") (pintype "passive"))
      (node (ref "C530") (pin "2") (pinfunction "2_2") (pintype "passive"))
      (node (ref "C531") (pin "1") (pinfunction "1_1") (pintype "passive"))
      (node (ref "C532") (pin "1") (pinfunction "1_1") (pintype "passive"))
      (node (ref "C533") (pin "1") (pinfunction "1_1") (pintype "passive"))
      (node (ref "C534") (pin "2") (pinfunction "2_2") (pintype "passive"))
      (node (ref "C535") (pin "2") (pinfunction "2_2") (pintype "passive"))
      (node (ref "C536") (pin "2") (pinfunction "2_2") (pintype "passive"))
      (node (ref "C537") (pin "2") (pinfunction "2_2") (pintype "passive"))
      (node (ref "C538") (pin "1") (pinfunction "1_1") (pintype "passive"))
      (node (ref "C539") (pin "2") (pinfunction "2_2") (pintype "passive"))
      (node (ref "C540") (pin "2") (pinfunction "2_2") (pintype "passive"))
      (node (ref "C541") (pin "2") (pinfunction "2_2") (pintype "passive"))
      (node (ref "C542") (pin "2") (pinfunction "2_2") (pintype "passive"))
      (node (ref "C543") (pin "1") (pinfunction "1_1") (pintype "passive"))
      (node (ref "C544") (pin "2") (pinfunction "2_2") (pintype "passive"))
      (node (ref "C545") (pin "1") (pinfunction "1_1") (pintype "passive"))
      (node (ref "C546") (pin "2") (pinfunction "2_2") (pintype "passive"))
      (node (ref "IC30") (pin "A2") (pinfunction "GND001_A2") (pintype "passive"))
      (node (ref "IC30") (pin "A24") (pinfunction "GND003_A24") (pintype "passive"))
      (node (ref "IC30") (pin "A5") (pinfunction "GND002_A5") (pintype "passive"))
      (node (ref "IC30") (pin "AB2") (pinfunction "GND135_AB2") (pintype "passive"))
      (node (ref "IC30") (pin "AB4") (pinfunction "GND136_AB4") (pintype "passive"))
      (node (ref "IC30") (pin "AD1") (pinfunction "GND137_AD1") (pintype "passive"))
      (node (ref "IC30") (pin "AD4") (pinfunction "GND138_AD4") (pintype "passive"))
      (node (ref "IC30") (pin "AE2") (pinfunction "GND139_AE2") (pintype "passive"))
      (node (ref "IC30") (pin "B10") (pinfunction "GND007_B10") (pintype "passive"))
      (node (ref "IC30") (pin "B13") (pinfunction "GND008_B13") (pintype "passive"))
      (node (ref "IC30") (pin "B16") (pinfunction "GND009_B16") (pintype "passive"))
      (node (ref "IC30") (pin "B19") (pinfunction "GND010_B19") (pintype "passive"))
      (node (ref "IC30") (pin "B21") (pinfunction "GND011_B21") (pintype "passive"))
      (node (ref "IC30") (pin "B25") (pinfunction "GND012_B25") (pintype "passive"))
      (node (ref "IC30") (pin "B3") (pinfunction "GND004_B3") (pintype "passive"))
      (node (ref "IC30") (pin "B4") (pinfunction "GND005_B4") (pintype "passive"))
      (node (ref "IC30") (pin "B7") (pinfunction "GND006_B7") (pintype "passive"))
      (node (ref "IC30") (pin "C1") (pinfunction "GND013_C1") (pintype "passive"))
      (node (ref "IC30") (pin "C2") (pinfunction "GND014_C2") (pintype "passive"))
      (node (ref "IC30") (pin "C23") (pinfunction "GND016_C23") (pintype "passive"))
      (node (ref "IC30") (pin "C5") (pinfunction "GND015_C5") (pintype "passive"))
      (node (ref "IC30") (pin "D12") (pinfunction "GND021_D12") (pintype "passive"))
      (node (ref "IC30") (pin "D15") (pinfunction "GND022_D15") (pintype "passive"))
      (node (ref "IC30") (pin "D18") (pinfunction "GND023_D18") (pintype "passive"))
      (node (ref "IC30") (pin "D21") (pinfunction "GND024_D21") (pintype "passive"))
      (node (ref "IC30") (pin "D3") (pinfunction "GND017_D3") (pintype "passive"))
      (node (ref "IC30") (pin "D4") (pinfunction "GND018_D4") (pintype "passive"))
      (node (ref "IC30") (pin "D7") (pinfunction "GND019_D7") (pintype "passive"))
      (node (ref "IC30") (pin "D9") (pinfunction "GND020_D9") (pintype "passive"))
      (node (ref "IC30") (pin "E1") (pinfunction "GND025_E1") (pintype "passive"))
      (node (ref "IC30") (pin "E2") (pinfunction "GND026_E2") (pintype "passive"))
      (node (ref "IC30") (pin "E22") (pinfunction "GND028_E22") (pintype "passive"))
      (node (ref "IC30") (pin "E24") (pinfunction "GND029_E24") (pintype "passive"))
      (node (ref "IC30") (pin "E5") (pinfunction "GND027_E5") (pintype "passive"))
      (node (ref "IC30") (pin "F11") (pinfunction "GND034_F11") (pintype "passive"))
      (node (ref "IC30") (pin "F12") (pinfunction "GND035_F12") (pintype "passive"))
      (node (ref "IC30") (pin "F13") (pinfunction "GND036_F13") (pintype "passive"))
      (node (ref "IC30") (pin "F17") (pinfunction "GND037_F17") (pintype "passive"))
      (node (ref "IC30") (pin "F20") (pinfunction "GND038_F20") (pintype "passive"))
      (node (ref "IC30") (pin "F3") (pinfunction "GND030_F3") (pintype "passive"))
      (node (ref "IC30") (pin "F4") (pinfunction "GND031_F4") (pintype "passive"))
      (node (ref "IC30") (pin "F7") (pinfunction "GND032_F7") (pintype "passive"))
      (node (ref "IC30") (pin "F8") (pinfunction "GND033_F8") (pintype "passive"))
      (node (ref "IC30") (pin "G1") (pinfunction "GND039_G1") (pintype "passive"))
      (node (ref "IC30") (pin "G2") (pinfunction "GND040_G2") (pintype "passive"))
      (node (ref "IC30") (pin "G22") (pinfunction "GND041_G22") (pintype "passive"))
      (node (ref "IC30") (pin "G24") (pinfunction "GND042_G24") (pintype "passive"))
      (node (ref "IC30") (pin "H10") (pinfunction "GND048_H10") (pintype "passive"))
      (node (ref "IC30") (pin "H11") (pinfunction "GND049_H11") (pintype "passive"))
      (node (ref "IC30") (pin "H12") (pinfunction "GND050_H12") (pintype "passive"))
      (node (ref "IC30") (pin "H13") (pinfunction "GND051_H13") (pintype "passive"))
      (node (ref "IC30") (pin "H14") (pinfunction "GND052_H14") (pintype "passive"))
      (node (ref "IC30") (pin "H15") (pinfunction "GND053_H15") (pintype "passive"))
      (node (ref "IC30") (pin "H16") (pinfunction "GND054_H16") (pintype "passive"))
      (node (ref "IC30") (pin "H17") (pinfunction "GND055_H17") (pintype "passive"))
      (node (ref "IC30") (pin "H3") (pinfunction "GND043_H3") (pintype "passive"))
      (node (ref "IC30") (pin "H4") (pinfunction "GND044_H4") (pintype "passive"))
      (node (ref "IC30") (pin "H5") (pinfunction "GND045_H5") (pintype "passive"))
      (node (ref "IC30") (pin "H8") (pinfunction "GND046_H8") (pintype "passive"))
      (node (ref "IC30") (pin "H9") (pinfunction "GND047_H9") (pintype "passive"))
      (node (ref "IC30") (pin "J19") (pinfunction "GND057_J19") (pintype "passive"))
      (node (ref "IC30") (pin "J20") (pinfunction "GND058_J20") (pintype "passive"))
      (node (ref "IC30") (pin "J24") (pinfunction "GND059_J24") (pintype "passive"))
      (node (ref "IC30") (pin "J7") (pinfunction "GND056_J7") (pintype "passive"))
      (node (ref "IC30") (pin "K10") (pinfunction "GND063_K10") (pintype "passive"))
      (node (ref "IC30") (pin "K12") (pinfunction "GND064_K12") (pintype "passive"))
      (node (ref "IC30") (pin "K14") (pinfunction "GND065_K14") (pintype "passive"))
      (node (ref "IC30") (pin "K16") (pinfunction "GND066_K16") (pintype "passive"))
      (node (ref "IC30") (pin "K19") (pinfunction "GND067_K19") (pintype "passive"))
      (node (ref "IC30") (pin "K2") (pinfunction "GND060_K2") (pintype "passive"))
      (node (ref "IC30") (pin "K22") (pinfunction "GND068_K22") (pintype "passive"))
      (node (ref "IC30") (pin "K4") (pinfunction "GND061_K4") (pintype "passive"))
      (node (ref "IC30") (pin "K7") (pinfunction "GND062_K7") (pintype "passive"))
      (node (ref "IC30") (pin "L11") (pinfunction "GND071_L11") (pintype "passive"))
      (node (ref "IC30") (pin "L13") (pinfunction "GND072_L13") (pintype "passive"))
      (node (ref "IC30") (pin "L15") (pinfunction "GND073_L15") (pintype "passive"))
      (node (ref "IC30") (pin "L17") (pinfunction "GND074_L17") (pintype "passive"))
      (node (ref "IC30") (pin "L19") (pinfunction "GND075_L19") (pintype "passive"))
      (node (ref "IC30") (pin "L7") (pinfunction "GND069_L7") (pintype "passive"))
      (node (ref "IC30") (pin "L9") (pinfunction "GND070_L9") (pintype "passive"))
      (node (ref "IC30") (pin "P10") (pinfunction "GND097_P10") (pintype "passive"))
      (node (ref "IC30") (pin "P12") (pinfunction "GND098_P12") (pintype "passive"))
      (node (ref "IC30") (pin "P14") (pinfunction "GND099_P14") (pintype "passive"))
      (node (ref "IC30") (pin "P16") (pinfunction "GND100_P16") (pintype "passive"))
      (node (ref "IC30") (pin "P19") (pinfunction "GND101_P19") (pintype "passive"))
      (node (ref "IC30") (pin "P22") (pinfunction "GND102_P22") (pintype "passive"))
      (node (ref "IC30") (pin "P24") (pinfunction "GND103_P24") (pintype "passive"))
      (node (ref "IC30") (pin "P8") (pinfunction "GND096_P8") (pintype "passive"))
      (node (ref "IC30") (pin "R11") (pinfunction "GND105_R11") (pintype "passive"))
      (node (ref "IC30") (pin "R13") (pinfunction "GND106_R13") (pintype "passive"))
      (node (ref "IC30") (pin "R15") (pinfunction "GND107_R15") (pintype "passive"))
      (node (ref "IC30") (pin "R17") (pinfunction "GND108_R17") (pintype "passive"))
      (node (ref "IC30") (pin "R19") (pinfunction "GND109_R19") (pintype "passive"))
      (node (ref "IC30") (pin "R25") (pinfunction "GND110_R25") (pintype "passive"))
      (node (ref "IC30") (pin "R9") (pinfunction "GND104_R9") (pintype "passive"))
      (node (ref "IC30") (pin "T10") (pinfunction "GND114_T10") (pintype "passive"))
      (node (ref "IC30") (pin "T12") (pinfunction "GND115_T12") (pintype "passive"))
      (node (ref "IC30") (pin "T14") (pinfunction "GND116_T14") (pintype "passive"))
      (node (ref "IC30") (pin "T2") (pinfunction "GND111_T2") (pintype "passive"))
      (node (ref "IC30") (pin "T20") (pinfunction "GND117_T20") (pintype "passive"))
      (node (ref "IC30") (pin "T4") (pinfunction "GND112_T4") (pintype "passive"))
      (node (ref "IC30") (pin "T8") (pinfunction "GND113_T8") (pintype "passive"))
      (node (ref "IC30") (pin "U11") (pinfunction "GND120_U11") (pintype "passive"))
      (node (ref "IC30") (pin "U20") (pinfunction "GND121_U20") (pintype "passive"))
      (node (ref "IC30") (pin "U6") (pinfunction "GND118_U6") (pintype "passive"))
      (node (ref "IC30") (pin "U9") (pinfunction "GND119_U9") (pintype "passive"))
      (node (ref "IC30") (pin "V10") (pinfunction "GND125_V10") (pintype "passive"))
      (node (ref "IC30") (pin "V11") (pinfunction "GND126_V11") (pintype "passive"))
      (node (ref "IC30") (pin "V12") (pinfunction "GND127_V12") (pintype "passive"))
      (node (ref "IC30") (pin "V13") (pinfunction "GND128_V13") (pintype "passive"))
      (node (ref "IC30") (pin "V14") (pinfunction "GND129_V14") (pintype "passive"))
      (node (ref "IC30") (pin "V2") (pinfunction "GND122_V2") (pintype "passive"))
      (node (ref "IC30") (pin "V20") (pinfunction "GND130_V20") (pintype "passive"))
      (node (ref "IC30") (pin "V8") (pinfunction "GND123_V8") (pintype "passive"))
      (node (ref "IC30") (pin "V9") (pinfunction "GND124_V9") (pintype "passive"))
      (node (ref "IC30") (pin "W20") (pinfunction "GND132_W20") (pintype "passive"))
      (node (ref "IC30") (pin "W4") (pinfunction "GND131_W4") (pintype "passive"))
      (node (ref "IC30") (pin "Y2") (pinfunction "GND133_Y2") (pintype "passive"))
      (node (ref "IC30") (pin "Y20") (pinfunction "GND134_Y20") (pintype "passive"))
      (node (ref "R260") (pin "1") (pinfunction "1_1") (pintype "passive"))
      (node (ref "R261") (pin "1") (pinfunction "1_1") (pintype "passive"))
      (node (ref "R262") (pin "1") (pinfunction "1_1") (pintype "passive"))
      (node (ref "R263") (pin "1") (pinfunction "1_1") (pintype "passive"))
    )
    (net (code "19") (name "Net-(C391-Pad1)") (class "Default")
      (node (ref "C391") (pin "1") (pinfunction "1_1") (pintype "passive"))
      (node (ref "C392") (pin "1") (pinfunction "1_1") (pintype "passive"))
      (node (ref "C393") (pin "2") (pinfunction "2_2") (pintype "passive"))
      (node (ref "C394") (pin "1") (pinfunction "1_1") (pintype "passive"))
    )
    (net (code "20") (name "Net-(C505-Pad1)") (class "Default")
      (node (ref "C505") (pin "1") (pinfunction "1_1") (pintype "passive"))
      (node (ref "C513") (pin "1") (pinfunction "1_1") (pintype "passive"))
      (node (ref "R264") (pin "1") (pinfunction "1_1") (pintype "passive"))
    )
    (net (code "21") (name "Net-(C511-Pad1)") (class "Default")
      (node (ref "C511") (pin "1") (pinfunction "1_1") (pintype "passive"))
      (node (ref "C512") (pin "2") (pinfunction "2_2") (pintype "passive"))
    )
    (net (code "22") (name "Net-(IC30G-LVDD2)") (class "Default")
      (node (ref "C506") (pin "1") (pinfunction "1_1") (pintype "passive"))
      (node (ref "C507") (pin "1") (pinfunction "1_1") (pintype "passive"))
      (node (ref "C508") (pin "2") (pinfunction "2_2") (pintype "passive"))
      (node (ref "C509") (pin "2") (pinfunction "2_2") (pintype "passive"))
      (node (ref "C510") (pin "2") (pinfunction "2_2") (pintype "passive"))
      (node (ref "IC30") (pin "U13") (pinfunction "LVDD2_U13") (pintype "passive"))
      (node (ref "IC30") (pin "U14") (pinfunction "LVDD3_U14") (pintype "passive"))
      (node (ref "L24") (pin "2") (pinfunction "2_2") (pintype "passive"))
    )
    (net (code "23") (name "Net-(IC30H-SENSEGND)") (class "Default")
      (node (ref "IC30") (pin "V7") (pinfunction "SENSEGND_V7") (pintype "passive"))
      (node (ref "R259") (pin "1") (pinfunction "1_1") (pintype "passive"))
    )
    (net (code "24") (name "Net-(IC30H-SENSEVDD)") (class "Default")
      (node (ref "IC30") (pin "W7") (pinfunction "SENSEVDD_W7") (pintype "passive"))
      (node (ref "R258") (pin "1") (pinfunction "1_1") (pintype "passive"))
    )
    (net (code "25") (name "Net-(IC30H-TVDD)") (class "Default")
      (node (ref "C453") (pin "2") (pinfunction "2_2") (pintype "passive"))
      (node (ref "C454") (pin "1") (pinfunction "1_1") (pintype "passive"))
      (node (ref "IC30") (pin "V6") (pinfunction "TVDD_V6") (pintype "passive"))
      (node (ref "L21") (pin "1") (pinfunction "1_1") (pintype "passive"))
    )
    (net (code "26") (name "PWR_X1VDD") (class "Default")
      (node (ref "C528") (pin "1") (pinfunction "1_1") (pintype "passive"))
      (node (ref "C529") (pin "1") (pinfunction "1_1") (pintype "passive"))
      (node (ref "C530") (pin "1") (pinfunction "1_1") (pintype "passive"))
      (node (ref "L26") (pin "2") (pinfunction "2_2") (pintype "passive"))
      (node (ref "L28") (pin "2") (pinfunction "2_2") (pintype "passive"))
    )
    (net (code "27") (name "S1VDD") (class "Default")
      (node (ref "C514") (pin "2") (pinfunction "2_2") (pintype "passive"))
      (node (ref "C515") (pin "2") (pinfunction "2_2") (pintype "passive"))
      (node (ref "C516") (pin "1") (pinfunction "1_1") (pintype "passive"))
      (node (ref "C517") (pin "1") (pinfunction "1_1") (pintype "passive"))
      (node (ref "C518") (pin "2") (pinfunction "2_2") (pintype "passive"))
      (node (ref "C519") (pin "2") (pinfunction "2_2") (pintype "passive"))
      (node (ref "C520") (pin "2") (pinfunction "2_2") (pintype "passive"))
      (node (ref "C521") (pin "2") (pinfunction "2_2") (pintype "passive"))
      (node (ref "IC30") (pin "T15") (pinfunction "S1VDD1_T15") (pintype "passive"))
      (node (ref "IC30") (pin "T16") (pinfunction "S1VDD2_T16") (pintype "passive"))
      (node (ref "IC30") (pin "T17") (pinfunction "S1VDD3_T17") (pintype "passive"))
      (node (ref "IC30") (pin "T18") (pinfunction "S1VDD4_T18") (pintype "passive"))
      (node (ref "L25") (pin "2") (pinfunction "2_2") (pintype "passive"))
      (node (ref "L27") (pin "2") (pinfunction "2_2") (pintype "passive"))
      (node (ref "L29") (pin "2") (pinfunction "2_2") (pintype "passive"))
      (node (ref "L30") (pin "2") (pinfunction "2_2") (pintype "passive"))
    )
    (net (code "28") (name "S1VDD_SRC") (class "Default")
      (node (ref "L29") (pin "1") (pinfunction "1_1") (pintype "passive"))
      (node (ref "L30") (pin "1") (pinfunction "1_1") (pintype "passive"))
    )
    (net (code "29") (name "VDD_FA_VDD") (class "Default")
      (node (ref "C505") (pin "2") (pinfunction "2_2") (pintype "passive"))
      (node (ref "C513") (pin "2") (pinfunction "2_2") (pintype "passive"))
      (node (ref "P9") (pin "1") (pinfunction "1_1") (pintype "passive"))
      (node (ref "R264") (pin "2") (pinfunction "2_2") (pintype "passive"))
    )
    (net (code "30") (name "VDD_LP") (class "Default")
      (node (ref "C451") (pin "1") (pinfunction "1_1") (pintype "passive"))
      (node (ref "C452") (pin "2") (pinfunction "2_2") (pintype "passive"))
      (node (ref "IC30") (pin "H20") (pinfunction "TA_BB_VDD_H20") (pintype "passive"))
      (node (ref "P6") (pin "1") (pinfunction "1_1") (pintype "passive"))
      (node (ref "R260") (pin "2") (pinfunction "2_2") (pintype "passive"))
    )
    (net (code "31") (name "VDD_USB_HVVD") (class "Default")
      (node (ref "C434") (pin "2") (pinfunction "2_2") (pintype "passive"))
      (node (ref "C435") (pin "2") (pinfunction "2_2") (pintype "passive"))
      (node (ref "C436") (pin "1") (pinfunction "1_1") (pintype "passive"))
      (node (ref "C437") (pin "2") (pinfunction "2_2") (pintype "passive"))
      (node (ref "IC30") (pin "J8") (pinfunction "USB_HVDD1_J8") (pintype "passive"))
      (node (ref "IC30") (pin "J9") (pinfunction "USB_HVDD2_J9") (pintype "passive"))
      (node (ref "L20") (pin "1") (pinfunction "1_1") (pintype "passive"))
    )
    (net (code "32") (name "VDD_USB_SDVDD") (class "Default")
      (node (ref "C417") (pin "2") (pinfunction "2_2") (pintype "passive"))
      (node (ref "C418") (pin "2") (pinfunction "2_2") (pintype "passive"))
      (node (ref "C419") (pin "1") (pinfunction "1_1") (pintype "passive"))
      (node (ref "C420") (pin "2") (pinfunction "2_2") (pintype "passive"))
      (node (ref "IC30") (pin "K11") (pinfunction "USB_SDVDD2_K11") (pintype "passive"))
      (node (ref "IC30") (pin "K9") (pinfunction "USB_SDVDD1_K9") (pintype "passive"))
      (node (ref "L19") (pin "1") (pinfunction "1_1") (pintype "passive"))
    )
    (net (code "33") (name "VDD_USB_SVDD") (class "Default")
      (node (ref "C391") (pin "2") (pinfunction "2_2") (pintype "passive"))
      (node (ref "C392") (pin "2") (pinfunction "2_2") (pintype "passive"))
      (node (ref "C393") (pin "1") (pinfunction "1_1") (pintype "passive"))
      (node (ref "C394") (pin "2") (pinfunction "2_2") (pintype "passive"))
      (node (ref "IC30") (pin "J10") (pinfunction "USB_SVDD1_J10") (pintype "passive"))
      (node (ref "IC30") (pin "J11") (pinfunction "USB_SVDD2_J11") (pintype "passive"))
      (node (ref "L18") (pin "1") (pinfunction "1_1") (pintype "passive"))
    )
    (net (code "34") (name "X1VDD") (class "Default")
      (node (ref "C522") (pin "2") (pinfunction "2_2") (pintype "passive"))
      (node (ref "C523") (pin "2") (pinfunction "2_2") (pintype "passive"))
      (node (ref "C524") (pin "2") (pinfunction "2_2") (pintype "passive"))
      (node (ref "C525") (pin "2") (pinfunction "2_2") (pintype "passive"))
      (node (ref "C526") (pin "1") (pinfunction "1_1") (pintype "passive"))
      (node (ref "C527") (pin "1") (pinfunction "1_1") (pintype "passive"))
      (node (ref "C531") (pin "2") (pinfunction "2_2") (pintype "passive"))
      (node (ref "C532") (pin "2") (pinfunction "2_2") (pintype "passive"))
      (node (ref "IC30") (pin "W15") (pinfunction "X1VDD1_W15") (pintype "passive"))
      (node (ref "IC30") (pin "W16") (pinfunction "X1VDD2_W16") (pintype "passive"))
      (node (ref "IC30") (pin "W17") (pinfunction "X1VDD3_W17") (pintype "passive"))
      (node (ref "IC30") (pin "W18") (pinfunction "X1VDD4_W18") (pintype "passive"))
      (node (ref "IC30") (pin "Y19") (pinfunction "X1VDD5_Y19") (pintype "passive"))
      (node (ref "L26") (pin "1") (pinfunction "1_1") (pintype "passive"))
      (node (ref "L28") (pin "1") (pinfunction "1_1") (pintype "passive"))
      (node (ref "R267") (pin "1") (pinfunction "1_1") (pintype "passive"))
      (node (ref "R268") (pin "1") (pinfunction "1_1") (pintype "passive"))
    )
    (net (code "35") (name "unconnected-(IC30G-FA_VL-PadR7)") (class "Default")
      (node (ref "IC30") (pin "R7") (pinfunction "FA_VL_R7") (pintype "passive"))
    )
    (net (code "36") (name "unconnected-(IC30G-LVDD1-PadU12)") (class "Default")
      (node (ref "IC30") (pin "U12") (pinfunction "LVDD1_U12") (pintype "passive"))
    )
    (net (code "37") (name "unconnected-(IC30G-TH_TPA-PadP5)") (class "Default")
      (node (ref "IC30") (pin "P5") (pinfunction "TH_TPA_P5") (pintype "passive+no_connect"))
    )
    (net (code "38") (name "unconnected-(IC30I-S1VDD5-PadW14)") (class "Default")
      (node (ref "IC30") (pin "W14") (pinfunction "S1VDD5_W14") (pintype "passive"))
    )
    (net (code "39") (name "unconnected-(IC30J-GND076-PadL20)") (class "Default")
      (node (ref "IC30") (pin "L20") (pinfunction "GND076_L20") (pintype "passive"))
    )
    (net (code "40") (name "unconnected-(IC30J-GND077-PadL24)") (class "Default")
      (node (ref "IC30") (pin "L24") (pinfunction "GND077_L24") (pintype "passive"))
    )
    (net (code "41") (name "unconnected-(IC30J-GND078-PadM7)") (class "Default")
      (node (ref "IC30") (pin "M7") (pinfunction "GND078_M7") (pintype "passive"))
    )
    (net (code "42") (name "unconnected-(IC30J-GND079-PadM10)") (class "Default")
      (node (ref "IC30") (pin "M10") (pinfunction "GND079_M10") (pintype "passive"))
    )
    (net (code "43") (name "unconnected-(IC30J-GND080-PadM12)") (class "Default")
      (node (ref "IC30") (pin "M12") (pinfunction "GND080_M12") (pintype "passive"))
    )
    (net (code "44") (name "unconnected-(IC30J-GND081-PadM14)") (class "Default")
      (node (ref "IC30") (pin "M14") (pinfunction "GND081_M14") (pintype "passive"))
    )
    (net (code "45") (name "unconnected-(IC30J-GND082-PadM16)") (class "Default")
      (node (ref "IC30") (pin "M16") (pinfunction "GND082_M16") (pintype "passive"))
    )
    (net (code "46") (name "unconnected-(IC30J-GND083-PadM19)") (class "Default")
      (node (ref "IC30") (pin "M19") (pinfunction "GND083_M19") (pintype "passive"))
    )
    (net (code "47") (name "unconnected-(IC30J-GND084-PadM22)") (class "Default")
      (node (ref "IC30") (pin "M22") (pinfunction "GND084_M22") (pintype "passive"))
    )
    (net (code "48") (name "unconnected-(IC30J-GND085-PadN2)") (class "Default")
      (node (ref "IC30") (pin "N2") (pinfunction "GND085_N2") (pintype "passive"))
    )
    (net (code "49") (name "unconnected-(IC30J-GND086-PadN4)") (class "Default")
      (node (ref "IC30") (pin "N4") (pinfunction "GND086_N4") (pintype "passive"))
    )
    (net (code "50") (name "unconnected-(IC30J-GND087-PadN6)") (class "Default")
      (node (ref "IC30") (pin "N6") (pinfunction "GND087_N6") (pintype "passive"))
    )
    (net (code "51") (name "unconnected-(IC30J-GND088-PadN9)") (class "Default")
      (node (ref "IC30") (pin "N9") (pinfunction "GND088_N9") (pintype "passive"))
    )
    (net (code "52") (name "unconnected-(IC30J-GND089-PadN11)") (class "Default")
      (node (ref "IC30") (pin "N11") (pinfunction "GND089_N11") (pintype "passive"))
    )
    (net (code "53") (name "unconnected-(IC30J-GND090-PadN13)") (class "Default")
      (node (ref "IC30") (pin "N13") (pinfunction "GND090_N13") (pintype "passive"))
    )
    (net (code "54") (name "unconnected-(IC30J-GND091-PadN15)") (class "Default")
      (node (ref "IC30") (pin "N15") (pinfunction "GND091_N15") (pintype "passive"))
    )
    (net (code "55") (name "unconnected-(IC30J-GND092-PadN17)") (class "Default")
      (node (ref "IC30") (pin "N17") (pinfunction "GND092_N17") (pintype "passive"))
    )
    (net (code "56") (name "unconnected-(IC30J-GND093-PadN19)") (class "Default")
      (node (ref "IC30") (pin "N19") (pinfunction "GND093_N19") (pintype "passive"))
    )
    (net (code "57") (name "unconnected-(IC30J-GND094-PadN20)") (class "Default")
      (node (ref "IC30") (pin "N20") (pinfunction "GND094_N20") (pintype "passive"))
    )
    (net (code "58") (name "unconnected-(IC30J-GND095-PadP7)") (class "Default")
      (node (ref "IC30") (pin "P7") (pinfunction "GND095_P7") (pintype "passive"))
    )
    (net (code "59") (name "unconnected-(IC30M-NC-PadAA5)") (class "Default")
      (node (ref "IC30") (pin "AA5") (pinfunction "NC_AA5") (pintype "passive"))
    )
    (net (code "60") (name "unconnected-(IC30M-NC-PadAA6)") (class "Default")
      (node (ref "IC30") (pin "AA6") (pinfunction "NC_AA6") (pintype "passive"))
    )
    (net (code "61") (name "unconnected-(IC30M-NC-PadAA7)") (class "Default")
      (node (ref "IC30") (pin "AA7") (pinfunction "NC_AA7") (pintype "passive"))
    )
    (net (code "62") (name "unconnected-(IC30M-NC-PadAA8)") (class "Default")
      (node (ref "IC30") (pin "AA8") (pinfunction "NC_AA8") (pintype "passive"))
    )
    (net (code "63") (name "unconnected-(IC30M-NC-PadAA9)") (class "Default")
      (node (ref "IC30") (pin "AA9") (pinfunction "NC_AA9") (pintype "passive"))
    )
    (net (code "64") (name "unconnected-(IC30M-NC-PadAA10)") (class "Default")
      (node (ref "IC30") (pin "AA10") (pinfunction "NC_AA10") (pintype "passive"))
    )
    (net (code "65") (name "unconnected-(IC30M-NC-PadAA11)") (class "Default")
      (node (ref "IC30") (pin "AA11") (pinfunction "NC_AA11") (pintype "passive"))
    )
    (net (code "66") (name "unconnected-(IC30M-NC-PadAA12)") (class "Default")
      (node (ref "IC30") (pin "AA12") (pinfunction "NC_AA12") (pintype "passive"))
    )
    (net (code "67") (name "unconnected-(IC30M-NC-PadAB5)") (class "Default")
      (node (ref "IC30") (pin "AB5") (pinfunction "NC_AB5") (pintype "passive"))
    )
    (net (code "68") (name "unconnected-(IC30M-NC-PadAB6)") (class "Default")
      (node (ref "IC30") (pin "AB6") (pinfunction "NC_AB6") (pintype "passive"))
    )
    (net (code "69") (name "unconnected-(IC30M-NC-PadAB7)") (class "Default")
      (node (ref "IC30") (pin "AB7") (pinfunction "NC_AB7") (pintype "passive"))
    )
    (net (code "70") (name "unconnected-(IC30M-NC-PadAB8)") (class "Default")
      (node (ref "IC30") (pin "AB8") (pinfunction "NC_AB8") (pintype "passive"))
    )
    (net (code "71") (name "unconnected-(IC30M-NC-PadAB9)") (class "Default")
      (node (ref "IC30") (pin "AB9") (pinfunction "NC_AB9") (pintype "passive"))
    )
    (net (code "72") (name "unconnected-(IC30M-NC-PadAB10)") (class "Default")
      (node (ref "IC30") (pin "AB10") (pinfunction "NC_AB10") (pintype "passive"))
    )
    (net (code "73") (name "unconnected-(IC30M-NC-PadAB11)") (class "Default")
      (node (ref "IC30") (pin "AB11") (pinfunction "NC_AB11") (pintype "passive"))
    )
    (net (code "74") (name "unconnected-(IC30M-NC-PadAB12)") (class "Default")
      (node (ref "IC30") (pin "AB12") (pinfunction "NC_AB12") (pintype "passive"))
    )
    (net (code "75") (name "unconnected-(IC30M-NC-PadAC5)") (class "Default")
      (node (ref "IC30") (pin "AC5") (pinfunction "NC_AC5") (pintype "passive"))
    )
    (net (code "76") (name "unconnected-(IC30M-NC-PadAC6)") (class "Default")
      (node (ref "IC30") (pin "AC6") (pinfunction "NC_AC6") (pintype "passive"))
    )
    (net (code "77") (name "unconnected-(IC30M-NC-PadAC7)") (class "Default")
      (node (ref "IC30") (pin "AC7") (pinfunction "NC_AC7") (pintype "passive"))
    )
    (net (code "78") (name "unconnected-(IC30M-NC-PadAC8)") (class "Default")
      (node (ref "IC30") (pin "AC8") (pinfunction "NC_AC8") (pintype "passive"))
    )
    (net (code "79") (name "unconnected-(IC30M-NC-PadAC9)") (class "Default")
      (node (ref "IC30") (pin "AC9") (pinfunction "NC_AC9") (pintype "passive"))
    )
    (net (code "80") (name "unconnected-(IC30M-NC-PadAC10)") (class "Default")
      (node (ref "IC30") (pin "AC10") (pinfunction "NC_AC10") (pintype "passive"))
    )
    (net (code "81") (name "unconnected-(IC30M-NC-PadAC11)") (class "Default")
      (node (ref "IC30") (pin "AC11") (pinfunction "NC_AC11") (pintype "passive"))
    )
    (net (code "82") (name "unconnected-(IC30M-NC-PadAC12)") (class "Default")
      (node (ref "IC30") (pin "AC12") (pinfunction "NC_AC12") (pintype "passive"))
    )
    (net (code "83") (name "unconnected-(IC30M-NC-PadAD5)") (class "Default")
      (node (ref "IC30") (pin "AD5") (pinfunction "NC_AD5") (pintype "passive"))
    )
    (net (code "84") (name "unconnected-(IC30M-NC-PadAD6)") (class "Default")
      (node (ref "IC30") (pin "AD6") (pinfunction "NC_AD6") (pintype "passive+no_connect"))
    )
    (net (code "85") (name "unconnected-(IC30M-NC-PadAD7)") (class "Default")
      (node (ref "IC30") (pin "AD7") (pinfunction "NC_AD7") (pintype "passive+no_connect"))
    )
    (net (code "86") (name "unconnected-(IC30M-NC-PadAD8)") (class "Default")
      (node (ref "IC30") (pin "AD8") (pinfunction "NC_AD8") (pintype "passive+no_connect"))
    )
    (net (code "87") (name "unconnected-(IC30M-NC-PadAD9)") (class "Default")
      (node (ref "IC30") (pin "AD9") (pinfunction "NC_AD9") (pintype "passive+no_connect"))
    )
    (net (code "88") (name "unconnected-(IC30M-NC-PadAD10)") (class "Default")
      (node (ref "IC30") (pin "AD10") (pinfunction "NC_AD10") (pintype "passive"))
    )
    (net (code "89") (name "unconnected-(IC30M-NC-PadAD11)") (class "Default")
      (node (ref "IC30") (pin "AD11") (pinfunction "NC_AD11") (pintype "passive"))
    )
    (net (code "90") (name "unconnected-(IC30M-NC-PadAD12)") (class "Default")
      (node (ref "IC30") (pin "AD12") (pinfunction "NC_AD12") (pintype "passive"))
    )
    (net (code "91") (name "unconnected-(IC30M-NC-PadAE5)") (class "Default")
      (node (ref "IC30") (pin "AE5") (pinfunction "NC_AE5") (pintype "passive+no_connect"))
    )
    (net (code "92") (name "unconnected-(IC30M-NC-PadAE6)") (class "Default")
      (node (ref "IC30") (pin "AE6") (pinfunction "NC_AE6") (pintype "passive+no_connect"))
    )
    (net (code "93") (name "unconnected-(IC30M-NC-PadAE7)") (class "Default")
      (node (ref "IC30") (pin "AE7") (pinfunction "NC_AE7") (pintype "passive+no_connect"))
    )
    (net (code "94") (name "unconnected-(IC30M-NC-PadAE8)") (class "Default")
      (node (ref "IC30") (pin "AE8") (pinfunction "NC_AE8") (pintype "passive+no_connect"))
    )
    (net (code "95") (name "unconnected-(IC30M-NC-PadAE9)") (class "Default")
      (node (ref "IC30") (pin "AE9") (pinfunction "NC_AE9") (pintype "passive+no_connect"))
    )
    (net (code "96") (name "unconnected-(IC30M-NC-PadAE10)") (class "Default")
      (node (ref "IC30") (pin "AE10") (pinfunction "NC_AE10") (pintype "passive+no_connect"))
    )
    (net (code "97") (name "unconnected-(IC30M-NC-PadAE11)") (class "Default")
      (node (ref "IC30") (pin "AE11") (pinfunction "NC_AE11") (pintype "passive+no_connect"))
    )
    (net (code "98") (name "unconnected-(IC30M-NC-PadAE12)") (class "Default")
      (node (ref "IC30") (pin "AE12") (pinfunction "NC_AE12") (pintype "passive+no_connect"))
    )
    (net (code "99") (name "unconnected-(IC30M-NC-PadK6)") (class "Default")
      (node (ref "IC30") (pin "K6") (pinfunction "NC_K6") (pintype "passive+no_connect"))
    )
    (net (code "100") (name "unconnected-(IC30M-NC-PadL6)") (class "Default")
      (node (ref "IC30") (pin "L6") (pinfunction "NC_L6") (pintype "passive+no_connect"))
    )
    (net (code "101") (name "unconnected-(IC30M-NC-PadM6)") (class "Default")
      (node (ref "IC30") (pin "M6") (pinfunction "NC_M6") (pintype "passive+no_connect"))
    )
    (net (code "102") (name "unconnected-(IC30M-NC-PadY7)") (class "Default")
      (node (ref "IC30") (pin "Y7") (pinfunction "NC_Y7") (pintype "passive+no_connect"))
    )
    (net (code "103") (name "unconnected-(IC30M-NC-PadY13)") (class "Default")
      (node (ref "IC30") (pin "Y13") (pinfunction "NC_Y13") (pintype "passive+no_connect"))
    )
  )
)
